# TRS-80.net
KiCad netlist of a schematic drawn in EAGLE
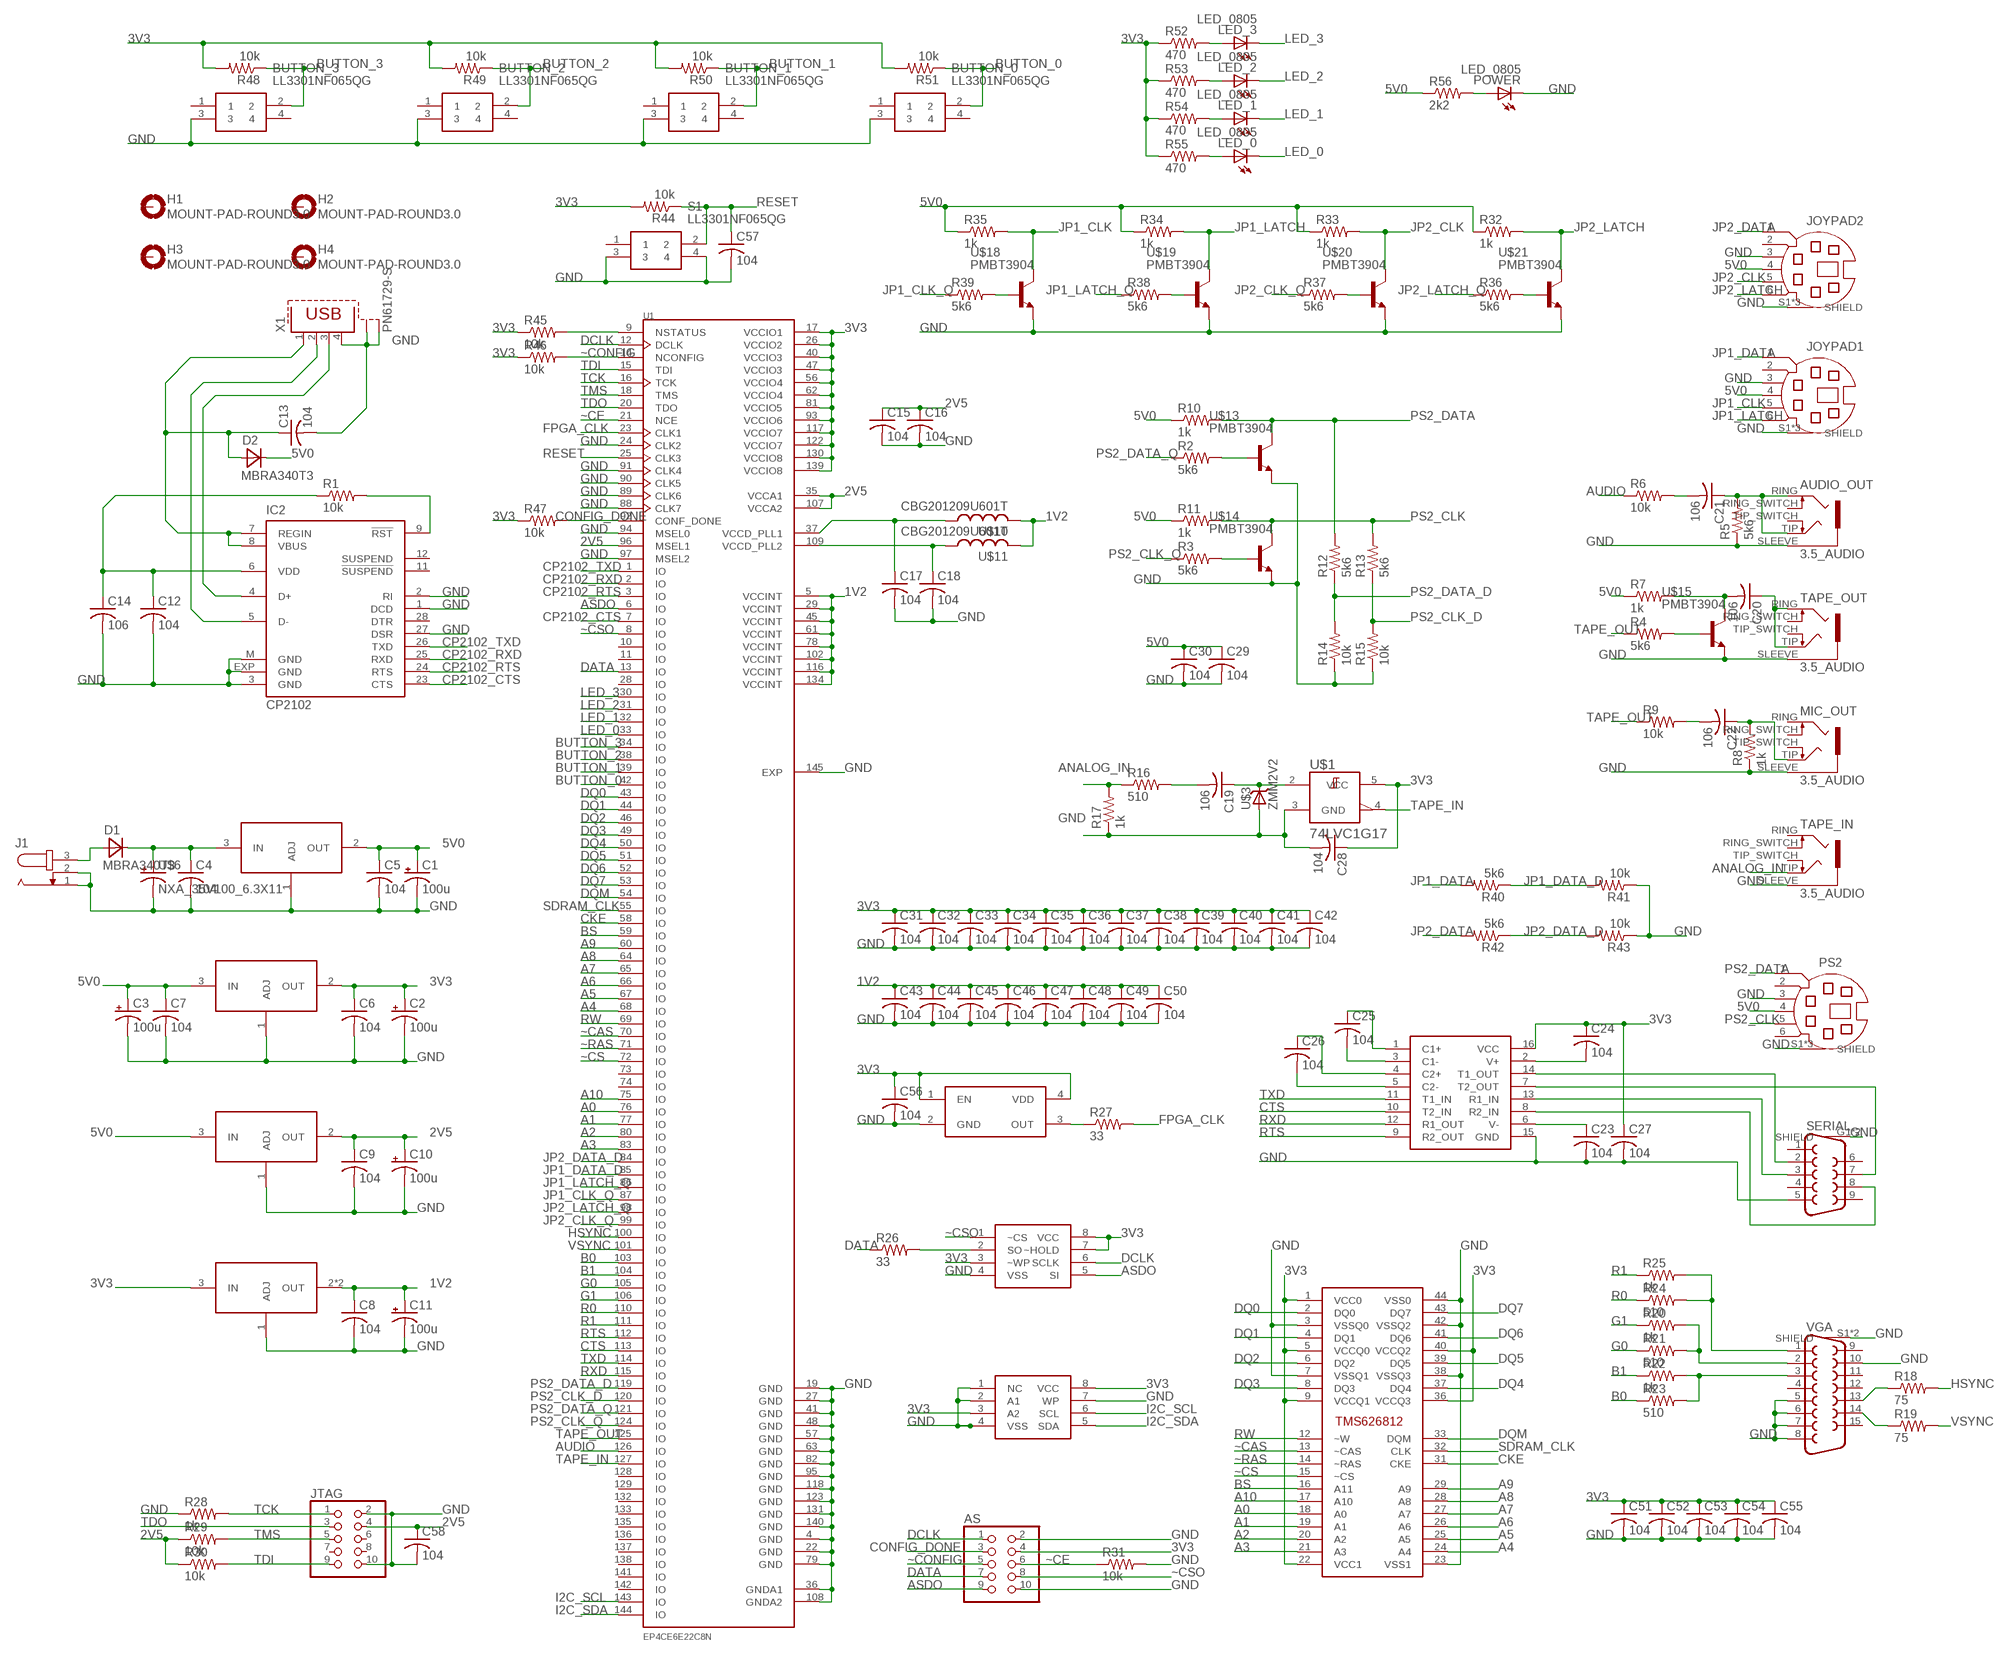
[diagram p0: schematic, sheet 1]

(export (version "E")
  (design (tool "Eeschema 10.0.6"))
  (components
    (comp (ref "AS")
      (value "PINHD-2X5")
      (footprint "eagle-import:2X05")
      (libsource (lib "eagle-import") (part "PINHD-2X5"))
    )
    (comp (ref "AUDIO_OUT")
      (value "3.5_AUDIO")
      (footprint "eagle-import:3.5_AUDIO")
      (libsource (lib "eagle-import") (part "3.5_AUDIO"))
    )
    (comp (ref "BUTTON_0")
      (value "LL3301NF065QG")
      (footprint "eagle-import:LL3301NF065QG")
      (fields (field (name "MOUSER_PART_NUMBER") "612-LL3301NF065QG"))
      (libsource (lib "eagle-import") (part "LL3301NF065QG"))
    )
    (comp (ref "BUTTON_1")
      (value "LL3301NF065QG")
      (footprint "eagle-import:LL3301NF065QG")
      (fields (field (name "MOUSER_PART_NUMBER") "612-LL3301NF065QG"))
      (libsource (lib "eagle-import") (part "LL3301NF065QG"))
    )
    (comp (ref "BUTTON_2")
      (value "LL3301NF065QG")
      (footprint "eagle-import:LL3301NF065QG")
      (fields (field (name "MOUSER_PART_NUMBER") "612-LL3301NF065QG"))
      (libsource (lib "eagle-import") (part "LL3301NF065QG"))
    )
    (comp (ref "BUTTON_3")
      (value "LL3301NF065QG")
      (footprint "eagle-import:LL3301NF065QG")
      (fields (field (name "MOUSER_PART_NUMBER") "612-LL3301NF065QG"))
      (libsource (lib "eagle-import") (part "LL3301NF065QG"))
    )
    (comp (ref "C1")
      (value "100u")
      (footprint "eagle-import:UD-6,3X5,8_NICHICON")
      (libsource (lib "eagle-import") (part "CPOL-USUD-6,3X5,8"))
    )
    (comp (ref "C2")
      (value "100u")
      (footprint "eagle-import:UD-6,3X5,8_NICHICON")
      (libsource (lib "eagle-import") (part "CPOL-USUD-6,3X5,8"))
    )
    (comp (ref "C3")
      (value "100u")
      (footprint "eagle-import:UD-6,3X5,8_NICHICON")
      (libsource (lib "eagle-import") (part "CPOL-USUD-6,3X5,8"))
    )
    (comp (ref "C4")
      (value "104")
      (footprint "eagle-import:C0805")
      (libsource (lib "eagle-import") (part "C-USC0805"))
    )
    (comp (ref "C5")
      (value "104")
      (footprint "eagle-import:C0805")
      (libsource (lib "eagle-import") (part "C-USC0805"))
    )
    (comp (ref "C6")
      (value "104")
      (footprint "eagle-import:C0805")
      (libsource (lib "eagle-import") (part "C-USC0805"))
    )
    (comp (ref "C7")
      (value "104")
      (footprint "eagle-import:C0805")
      (libsource (lib "eagle-import") (part "C-USC0805"))
    )
    (comp (ref "C8")
      (value "104")
      (footprint "eagle-import:C0805")
      (libsource (lib "eagle-import") (part "C-USC0805"))
    )
    (comp (ref "C9")
      (value "104")
      (footprint "eagle-import:C0805")
      (libsource (lib "eagle-import") (part "C-USC0805"))
    )
    (comp (ref "C10")
      (value "100u")
      (footprint "eagle-import:UD-6,3X5,8_NICHICON")
      (libsource (lib "eagle-import") (part "CPOL-USUD-6,3X5,8"))
    )
    (comp (ref "C11")
      (value "100u")
      (footprint "eagle-import:UD-6,3X5,8_NICHICON")
      (libsource (lib "eagle-import") (part "CPOL-USUD-6,3X5,8"))
    )
    (comp (ref "C12")
      (value "104")
      (footprint "eagle-import:C0805")
      (libsource (lib "eagle-import") (part "C-USC0805"))
    )
    (comp (ref "C13")
      (value "104")
      (footprint "eagle-import:C0805")
      (libsource (lib "eagle-import") (part "C-USC0805"))
    )
    (comp (ref "C14")
      (value "106")
      (footprint "eagle-import:C1206")
      (libsource (lib "eagle-import") (part "C-USC1206"))
    )
    (comp (ref "C15")
      (value "104")
      (footprint "eagle-import:C0805")
      (libsource (lib "eagle-import") (part "C-USC0805"))
    )
    (comp (ref "C16")
      (value "104")
      (footprint "eagle-import:C0805")
      (libsource (lib "eagle-import") (part "C-USC0805"))
    )
    (comp (ref "C17")
      (value "104")
      (footprint "eagle-import:C0805")
      (libsource (lib "eagle-import") (part "C-USC0805"))
    )
    (comp (ref "C18")
      (value "104")
      (footprint "eagle-import:C0805")
      (libsource (lib "eagle-import") (part "C-USC0805"))
    )
    (comp (ref "C19")
      (value "106")
      (footprint "eagle-import:C1206")
      (libsource (lib "eagle-import") (part "C-USC1206"))
    )
    (comp (ref "C20")
      (value "106")
      (footprint "eagle-import:C1206")
      (libsource (lib "eagle-import") (part "C-USC1206"))
    )
    (comp (ref "C21")
      (value "106")
      (footprint "eagle-import:C1206")
      (libsource (lib "eagle-import") (part "C-USC1206"))
    )
    (comp (ref "C22")
      (value "106")
      (footprint "eagle-import:C1206")
      (libsource (lib "eagle-import") (part "C-USC1206"))
    )
    (comp (ref "C23")
      (value "104")
      (footprint "eagle-import:C0805")
      (libsource (lib "eagle-import") (part "C-USC0805"))
    )
    (comp (ref "C24")
      (value "104")
      (footprint "eagle-import:C0805")
      (libsource (lib "eagle-import") (part "C-USC0805"))
    )
    (comp (ref "C25")
      (value "104")
      (footprint "eagle-import:C0805")
      (libsource (lib "eagle-import") (part "C-USC0805"))
    )
    (comp (ref "C26")
      (value "104")
      (footprint "eagle-import:C0805")
      (libsource (lib "eagle-import") (part "C-USC0805"))
    )
    (comp (ref "C27")
      (value "104")
      (footprint "eagle-import:C0805")
      (libsource (lib "eagle-import") (part "C-USC0805"))
    )
    (comp (ref "C28")
      (value "104")
      (footprint "eagle-import:C0805")
      (libsource (lib "eagle-import") (part "C-USC0805"))
    )
    (comp (ref "C29")
      (value "104")
      (footprint "eagle-import:C0805")
      (libsource (lib "eagle-import") (part "C-USC0805"))
    )
    (comp (ref "C30")
      (value "104")
      (footprint "eagle-import:C0805")
      (libsource (lib "eagle-import") (part "C-USC0805"))
    )
    (comp (ref "C31")
      (value "104")
      (footprint "eagle-import:C0805")
      (libsource (lib "eagle-import") (part "C-USC0805"))
    )
    (comp (ref "C32")
      (value "104")
      (footprint "eagle-import:C0805")
      (libsource (lib "eagle-import") (part "C-USC0805"))
    )
    (comp (ref "C33")
      (value "104")
      (footprint "eagle-import:C0805")
      (libsource (lib "eagle-import") (part "C-USC0805"))
    )
    (comp (ref "C34")
      (value "104")
      (footprint "eagle-import:C0805")
      (libsource (lib "eagle-import") (part "C-USC0805"))
    )
    (comp (ref "C35")
      (value "104")
      (footprint "eagle-import:C0805")
      (libsource (lib "eagle-import") (part "C-USC0805"))
    )
    (comp (ref "C36")
      (value "104")
      (footprint "eagle-import:C0805")
      (libsource (lib "eagle-import") (part "C-USC0805"))
    )
    (comp (ref "C37")
      (value "104")
      (footprint "eagle-import:C0805")
      (libsource (lib "eagle-import") (part "C-USC0805"))
    )
    (comp (ref "C38")
      (value "104")
      (footprint "eagle-import:C0805")
      (libsource (lib "eagle-import") (part "C-USC0805"))
    )
    (comp (ref "C39")
      (value "104")
      (footprint "eagle-import:C0805")
      (libsource (lib "eagle-import") (part "C-USC0805"))
    )
    (comp (ref "C40")
      (value "104")
      (footprint "eagle-import:C0805")
      (libsource (lib "eagle-import") (part "C-USC0805"))
    )
    (comp (ref "C41")
      (value "104")
      (footprint "eagle-import:C0805")
      (libsource (lib "eagle-import") (part "C-USC0805"))
    )
    (comp (ref "C42")
      (value "104")
      (footprint "eagle-import:C0805")
      (libsource (lib "eagle-import") (part "C-USC0805"))
    )
    (comp (ref "C43")
      (value "104")
      (footprint "eagle-import:C0805")
      (libsource (lib "eagle-import") (part "C-USC0805"))
    )
    (comp (ref "C44")
      (value "104")
      (footprint "eagle-import:C0805")
      (libsource (lib "eagle-import") (part "C-USC0805"))
    )
    (comp (ref "C45")
      (value "104")
      (footprint "eagle-import:C0805")
      (libsource (lib "eagle-import") (part "C-USC0805"))
    )
    (comp (ref "C46")
      (value "104")
      (footprint "eagle-import:C0805")
      (libsource (lib "eagle-import") (part "C-USC0805"))
    )
    (comp (ref "C47")
      (value "104")
      (footprint "eagle-import:C0805")
      (libsource (lib "eagle-import") (part "C-USC0805"))
    )
    (comp (ref "C48")
      (value "104")
      (footprint "eagle-import:C0805")
      (libsource (lib "eagle-import") (part "C-USC0805"))
    )
    (comp (ref "C49")
      (value "104")
      (footprint "eagle-import:C0805")
      (libsource (lib "eagle-import") (part "C-USC0805"))
    )
    (comp (ref "C50")
      (value "104")
      (footprint "eagle-import:C0805")
      (libsource (lib "eagle-import") (part "C-USC0805"))
    )
    (comp (ref "C51")
      (value "104")
      (footprint "eagle-import:C0805")
      (libsource (lib "eagle-import") (part "C-USC0805"))
    )
    (comp (ref "C52")
      (value "104")
      (footprint "eagle-import:C0805")
      (libsource (lib "eagle-import") (part "C-USC0805"))
    )
    (comp (ref "C53")
      (value "104")
      (footprint "eagle-import:C0805")
      (libsource (lib "eagle-import") (part "C-USC0805"))
    )
    (comp (ref "C54")
      (value "104")
      (footprint "eagle-import:C0805")
      (libsource (lib "eagle-import") (part "C-USC0805"))
    )
    (comp (ref "C55")
      (value "104")
      (footprint "eagle-import:C0805")
      (libsource (lib "eagle-import") (part "C-USC0805"))
    )
    (comp (ref "C56")
      (value "104")
      (footprint "eagle-import:C0805")
      (libsource (lib "eagle-import") (part "C-USC0805"))
    )
    (comp (ref "C57")
      (value "104")
      (footprint "eagle-import:C0805")
      (libsource (lib "eagle-import") (part "C-USC0805"))
    )
    (comp (ref "C58")
      (value "104")
      (footprint "eagle-import:C0805")
      (libsource (lib "eagle-import") (part "C-USC0805"))
    )
    (comp (ref "D1")
      (value "MBRA340T3")
      (footprint "eagle-import:SMA")
      (libsource (lib "eagle-import") (part "MBRA340T3"))
    )
    (comp (ref "D2")
      (value "MBRA340T3")
      (footprint "eagle-import:SMA")
      (libsource (lib "eagle-import") (part "MBRA340T3"))
    )
    (comp (ref "H1")
      (value "MOUNT-PAD-ROUND3.0")
      (footprint "eagle-import:3,0-PAD")
      (libsource (lib "eagle-import") (part "MOUNT-PAD-ROUND3.0"))
    )
    (comp (ref "H2")
      (value "MOUNT-PAD-ROUND3.0")
      (footprint "eagle-import:3,0-PAD")
      (libsource (lib "eagle-import") (part "MOUNT-PAD-ROUND3.0"))
    )
    (comp (ref "H3")
      (value "MOUNT-PAD-ROUND3.0")
      (footprint "eagle-import:3,0-PAD")
      (libsource (lib "eagle-import") (part "MOUNT-PAD-ROUND3.0"))
    )
    (comp (ref "H4")
      (value "MOUNT-PAD-ROUND3.0")
      (footprint "eagle-import:3,0-PAD")
      (libsource (lib "eagle-import") (part "MOUNT-PAD-ROUND3.0"))
    )
    (comp (ref "IC2")
      (value "CP2102")
      (footprint "eagle-import:MLP28")
      (fields (field (name "MF") "FARNELL") (field (name "MPN") "CP2102-GM"))
      (libsource (lib "eagle-import") (part "CP2102"))
    )
    (comp (ref "J1")
      (value "JACK-PLUG1")
      (footprint "eagle-import:SPC4078")
      (libsource (lib "eagle-import") (part "JACK-PLUG1"))
    )
    (comp (ref "JOYPAD1")
      (value "MD06SS")
      (footprint "eagle-import:MDIN06SS")
      (libsource (lib "eagle-import") (part "MD06SS"))
    )
    (comp (ref "JOYPAD2")
      (value "MD06SS")
      (footprint "eagle-import:MDIN06SS")
      (libsource (lib "eagle-import") (part "MD06SS"))
    )
    (comp (ref "JTAG")
      (value "PINHD-2X5")
      (footprint "eagle-import:2X05")
      (libsource (lib "eagle-import") (part "PINHD-2X5"))
    )
    (comp (ref "LED_0")
      (value "LED_0805")
      (footprint "eagle-import:CHIP-LED0805")
      (libsource (lib "eagle-import") (part "LED_0805"))
    )
    (comp (ref "LED_1")
      (value "LED_0805")
      (footprint "eagle-import:CHIP-LED0805")
      (libsource (lib "eagle-import") (part "LED_0805"))
    )
    (comp (ref "LED_2")
      (value "LED_0805")
      (footprint "eagle-import:CHIP-LED0805")
      (libsource (lib "eagle-import") (part "LED_0805"))
    )
    (comp (ref "LED_3")
      (value "LED_0805")
      (footprint "eagle-import:CHIP-LED0805")
      (libsource (lib "eagle-import") (part "LED_0805"))
    )
    (comp (ref "MIC_OUT")
      (value "3.5_AUDIO")
      (footprint "eagle-import:3.5_AUDIO")
      (libsource (lib "eagle-import") (part "3.5_AUDIO"))
    )
    (comp (ref "POWER")
      (value "LED_0805")
      (footprint "eagle-import:CHIP-LED0805")
      (libsource (lib "eagle-import") (part "LED_0805"))
    )
    (comp (ref "PS2")
      (value "MD06SS")
      (footprint "eagle-import:MDIN06SS")
      (libsource (lib "eagle-import") (part "MD06SS"))
    )
    (comp (ref "R1")
      (value "10k")
      (footprint "eagle-import:R0805")
      (libsource (lib "eagle-import") (part "R-US_R0805"))
    )
    (comp (ref "R2")
      (value "5k6")
      (footprint "eagle-import:R0805")
      (libsource (lib "eagle-import") (part "R-US_R0805"))
    )
    (comp (ref "R3")
      (value "5k6")
      (footprint "eagle-import:R0805")
      (libsource (lib "eagle-import") (part "R-US_R0805"))
    )
    (comp (ref "R4")
      (value "5k6")
      (footprint "eagle-import:R0805")
      (libsource (lib "eagle-import") (part "R-US_R0805"))
    )
    (comp (ref "R5")
      (value "5k6")
      (footprint "eagle-import:R0805")
      (libsource (lib "eagle-import") (part "R-US_R0805"))
    )
    (comp (ref "R6")
      (value "10k")
      (footprint "eagle-import:R0805")
      (libsource (lib "eagle-import") (part "R-US_R0805"))
    )
    (comp (ref "R7")
      (value "1k")
      (footprint "eagle-import:R0805")
      (libsource (lib "eagle-import") (part "R-US_R0805"))
    )
    (comp (ref "R8")
      (value "1k")
      (footprint "eagle-import:R0805")
      (libsource (lib "eagle-import") (part "R-US_R0805"))
    )
    (comp (ref "R9")
      (value "10k")
      (footprint "eagle-import:R0805")
      (libsource (lib "eagle-import") (part "R-US_R0805"))
    )
    (comp (ref "R10")
      (value "1k")
      (footprint "eagle-import:R0805")
      (libsource (lib "eagle-import") (part "R-US_R0805"))
    )
    (comp (ref "R11")
      (value "1k")
      (footprint "eagle-import:R0805")
      (libsource (lib "eagle-import") (part "R-US_R0805"))
    )
    (comp (ref "R12")
      (value "5k6")
      (footprint "eagle-import:R0805")
      (libsource (lib "eagle-import") (part "R-US_R0805"))
    )
    (comp (ref "R13")
      (value "5k6")
      (footprint "eagle-import:R0805")
      (libsource (lib "eagle-import") (part "R-US_R0805"))
    )
    (comp (ref "R14")
      (value "10k")
      (footprint "eagle-import:R0805")
      (libsource (lib "eagle-import") (part "R-US_R0805"))
    )
    (comp (ref "R15")
      (value "10k")
      (footprint "eagle-import:R0805")
      (libsource (lib "eagle-import") (part "R-US_R0805"))
    )
    (comp (ref "R16")
      (value "510")
      (footprint "eagle-import:R0805")
      (libsource (lib "eagle-import") (part "R-US_R0805"))
    )
    (comp (ref "R17")
      (value "1k")
      (footprint "eagle-import:R0805")
      (libsource (lib "eagle-import") (part "R-US_R0805"))
    )
    (comp (ref "R18")
      (value "75")
      (footprint "eagle-import:R0805")
      (libsource (lib "eagle-import") (part "R-US_R0805"))
    )
    (comp (ref "R19")
      (value "75")
      (footprint "eagle-import:R0805")
      (libsource (lib "eagle-import") (part "R-US_R0805"))
    )
    (comp (ref "R20")
      (value "1k")
      (footprint "eagle-import:R0805")
      (libsource (lib "eagle-import") (part "R-US_R0805"))
    )
    (comp (ref "R21")
      (value "510")
      (footprint "eagle-import:R0805")
      (libsource (lib "eagle-import") (part "R-US_R0805"))
    )
    (comp (ref "R22")
      (value "1k")
      (footprint "eagle-import:R0805")
      (libsource (lib "eagle-import") (part "R-US_R0805"))
    )
    (comp (ref "R23")
      (value "510")
      (footprint "eagle-import:R0805")
      (libsource (lib "eagle-import") (part "R-US_R0805"))
    )
    (comp (ref "R24")
      (value "510")
      (footprint "eagle-import:R0805")
      (libsource (lib "eagle-import") (part "R-US_R0805"))
    )
    (comp (ref "R25")
      (value "1k")
      (footprint "eagle-import:R0805")
      (libsource (lib "eagle-import") (part "R-US_R0805"))
    )
    (comp (ref "R26")
      (value "33")
      (footprint "eagle-import:R0805")
      (libsource (lib "eagle-import") (part "R-US_R0805"))
    )
    (comp (ref "R27")
      (value "33")
      (footprint "eagle-import:R0805")
      (libsource (lib "eagle-import") (part "R-US_R0805"))
    )
    (comp (ref "R28")
      (value "1k")
      (footprint "eagle-import:R0805")
      (libsource (lib "eagle-import") (part "R-US_R0805"))
    )
    (comp (ref "R29")
      (value "10k")
      (footprint "eagle-import:R0805")
      (libsource (lib "eagle-import") (part "R-US_R0805"))
    )
    (comp (ref "R30")
      (value "10k")
      (footprint "eagle-import:R0805")
      (libsource (lib "eagle-import") (part "R-US_R0805"))
    )
    (comp (ref "R31")
      (value "10k")
      (footprint "eagle-import:R0805")
      (libsource (lib "eagle-import") (part "R-US_R0805"))
    )
    (comp (ref "R32")
      (value "1k")
      (footprint "eagle-import:R0805")
      (libsource (lib "eagle-import") (part "R-US_R0805"))
    )
    (comp (ref "R33")
      (value "1k")
      (footprint "eagle-import:R0805")
      (libsource (lib "eagle-import") (part "R-US_R0805"))
    )
    (comp (ref "R34")
      (value "1k")
      (footprint "eagle-import:R0805")
      (libsource (lib "eagle-import") (part "R-US_R0805"))
    )
    (comp (ref "R35")
      (value "1k")
      (footprint "eagle-import:R0805")
      (libsource (lib "eagle-import") (part "R-US_R0805"))
    )
    (comp (ref "R36")
      (value "5k6")
      (footprint "eagle-import:R0805")
      (libsource (lib "eagle-import") (part "R-US_R0805"))
    )
    (comp (ref "R37")
      (value "5k6")
      (footprint "eagle-import:R0805")
      (libsource (lib "eagle-import") (part "R-US_R0805"))
    )
    (comp (ref "R38")
      (value "5k6")
      (footprint "eagle-import:R0805")
      (libsource (lib "eagle-import") (part "R-US_R0805"))
    )
    (comp (ref "R39")
      (value "5k6")
      (footprint "eagle-import:R0805")
      (libsource (lib "eagle-import") (part "R-US_R0805"))
    )
    (comp (ref "R40")
      (value "5k6")
      (footprint "eagle-import:R0805")
      (libsource (lib "eagle-import") (part "R-US_R0805"))
    )
    (comp (ref "R41")
      (value "10k")
      (footprint "eagle-import:R0805")
      (libsource (lib "eagle-import") (part "R-US_R0805"))
    )
    (comp (ref "R42")
      (value "5k6")
      (footprint "eagle-import:R0805")
      (libsource (lib "eagle-import") (part "R-US_R0805"))
    )
    (comp (ref "R43")
      (value "10k")
      (footprint "eagle-import:R0805")
      (libsource (lib "eagle-import") (part "R-US_R0805"))
    )
    (comp (ref "R44")
      (value "10k")
      (footprint "eagle-import:R0805")
      (libsource (lib "eagle-import") (part "R-US_R0805"))
    )
    (comp (ref "R45")
      (value "10k")
      (footprint "eagle-import:R0805")
      (libsource (lib "eagle-import") (part "R-US_R0805"))
    )
    (comp (ref "R46")
      (value "10k")
      (footprint "eagle-import:R0805")
      (libsource (lib "eagle-import") (part "R-US_R0805"))
    )
    (comp (ref "R47")
      (value "10k")
      (footprint "eagle-import:R0805")
      (libsource (lib "eagle-import") (part "R-US_R0805"))
    )
    (comp (ref "R48")
      (value "10k")
      (footprint "eagle-import:R0805")
      (libsource (lib "eagle-import") (part "R-US_R0805"))
    )
    (comp (ref "R49")
      (value "10k")
      (footprint "eagle-import:R0805")
      (libsource (lib "eagle-import") (part "R-US_R0805"))
    )
    (comp (ref "R50")
      (value "10k")
      (footprint "eagle-import:R0805")
      (libsource (lib "eagle-import") (part "R-US_R0805"))
    )
    (comp (ref "R51")
      (value "10k")
      (footprint "eagle-import:R0805")
      (libsource (lib "eagle-import") (part "R-US_R0805"))
    )
    (comp (ref "R52")
      (value "470")
      (footprint "eagle-import:R0805")
      (libsource (lib "eagle-import") (part "R-US_R0805"))
    )
    (comp (ref "R53")
      (value "470")
      (footprint "eagle-import:R0805")
      (libsource (lib "eagle-import") (part "R-US_R0805"))
    )
    (comp (ref "R54")
      (value "470")
      (footprint "eagle-import:R0805")
      (libsource (lib "eagle-import") (part "R-US_R0805"))
    )
    (comp (ref "R55")
      (value "470")
      (footprint "eagle-import:R0805")
      (libsource (lib "eagle-import") (part "R-US_R0805"))
    )
    (comp (ref "R56")
      (value "2k2")
      (footprint "eagle-import:R0805")
      (libsource (lib "eagle-import") (part "R-US_R0805"))
    )
    (comp (ref "S1")
      (value "LL3301NF065QG")
      (footprint "eagle-import:LL3301NF065QG")
      (fields (field (name "MOUSER_PART_NUMBER") "612-LL3301NF065QG"))
      (libsource (lib "eagle-import") (part "LL3301NF065QG"))
    )
    (comp (ref "SERIAL")
      (value "F09HP")
      (footprint "eagle-import:F09HP")
      (libsource (lib "eagle-import") (part "F09HP"))
    )
    (comp (ref "TAPE_IN")
      (value "3.5_AUDIO")
      (footprint "eagle-import:3.5_AUDIO")
      (libsource (lib "eagle-import") (part "3.5_AUDIO"))
    )
    (comp (ref "TAPE_OUT")
      (value "3.5_AUDIO")
      (footprint "eagle-import:3.5_AUDIO")
      (libsource (lib "eagle-import") (part "3.5_AUDIO"))
    )
    (comp (ref "U$1")
      (value "74LVC1G17")
      (footprint "eagle-import:SOT353")
      (libsource (lib "eagle-import") (part "74LVC1G17"))
    )
    (comp (ref "U$2")
      (value "TMS626812")
      (footprint "eagle-import:TSOP44-II")
      (libsource (lib "eagle-import") (part "TMS626812"))
    )
    (comp (ref "U$3")
      (value "ZMM2V2")
      (footprint "eagle-import:SOD80C")
      (libsource (lib "eagle-import") (part "ZMM2V2"))
    )
    (comp (ref "U$4")
      (value "SP232")
      (footprint "eagle-import:SOP16")
      (libsource (lib "eagle-import") (part "SP232"))
    )
    (comp (ref "U$5")
      (value "LM1086")
      (footprint "eagle-import:D2PACK")
      (libsource (lib "eagle-import") (part "LM1086"))
    )
    (comp (ref "U$6")
      (value "NXA_35V100_6.3X11")
      (footprint "eagle-import:NXA_35V100_6.3X11")
      (libsource (lib "eagle-import") (part "NXA_35V100_6.3X11"))
    )
    (comp (ref "U$7")
      (value "LD1117D-3.3")
      (footprint "eagle-import:TO252")
      (libsource (lib "eagle-import") (part "LD1117D-3.3"))
    )
    (comp (ref "U$8")
      (value "KIA1117-2.5")
      (footprint "eagle-import:SOT223")
      (libsource (lib "eagle-import") (part "KIA1117-2.5"))
    )
    (comp (ref "U$9")
      (value "AZ1117H-1.2TRG1")
      (footprint "eagle-import:SOT223")
      (libsource (lib "eagle-import") (part "AZ1117H-1.2TRG1"))
    )
    (comp (ref "U$10")
      (value "CBG201209U601T")
      (footprint "eagle-import:C0805")
      (libsource (lib "eagle-import") (part "CBG201209U601T"))
    )
    (comp (ref "U$11")
      (value "CBG201209U601T")
      (footprint "eagle-import:C0805")
      (libsource (lib "eagle-import") (part "CBG201209U601T"))
    )
    (comp (ref "U$12")
      (value "OT705050MJBA4SL")
      (footprint "eagle-import:ASV32000MHZET")
      (libsource (lib "eagle-import") (part "OT705050MJBA4SL"))
    )
    (comp (ref "U$13")
      (value "PMBT3904")
      (footprint "eagle-import:SOT23")
      (libsource (lib "eagle-import") (part "PMBT3904"))
    )
    (comp (ref "U$14")
      (value "PMBT3904")
      (footprint "eagle-import:SOT23")
      (libsource (lib "eagle-import") (part "PMBT3904"))
    )
    (comp (ref "U$15")
      (value "PMBT3904")
      (footprint "eagle-import:SOT23")
      (libsource (lib "eagle-import") (part "PMBT3904"))
    )
    (comp (ref "U$16")
      (value "BY25Q16BS")
      (footprint "eagle-import:SO08")
      (libsource (lib "eagle-import") (part "BY25Q16BS"))
    )
    (comp (ref "U$17")
      (value "CAT24M01WI-GT3")
      (footprint "eagle-import:SO08")
      (libsource (lib "eagle-import") (part "CAT24M01WI-GT3"))
    )
    (comp (ref "U$18")
      (value "PMBT3904")
      (footprint "eagle-import:SOT23")
      (libsource (lib "eagle-import") (part "PMBT3904"))
    )
    (comp (ref "U$19")
      (value "PMBT3904")
      (footprint "eagle-import:SOT23")
      (libsource (lib "eagle-import") (part "PMBT3904"))
    )
    (comp (ref "U$20")
      (value "PMBT3904")
      (footprint "eagle-import:SOT23")
      (libsource (lib "eagle-import") (part "PMBT3904"))
    )
    (comp (ref "U$21")
      (value "PMBT3904")
      (footprint "eagle-import:SOT23")
      (libsource (lib "eagle-import") (part "PMBT3904"))
    )
    (comp (ref "U1")
      (value "EP4CE6E22C8N")
      (footprint "eagle-import:QFP50P2200X2200X165-145N")
      (fields (field (name "MF") "Intel"))
      (libsource (lib "eagle-import") (part "EP4CE6E22C8N"))
    )
    (comp (ref "VGA")
      (value "F15HDH")
      (footprint "eagle-import:HDF15H")
      (libsource (lib "eagle-import") (part "F15HDH"))
    )
    (comp (ref "X1")
      (value "PN61729-S")
      (footprint "eagle-import:PN61729-S")
      (libsource (lib "eagle-import") (part "PN61729-S"))
    )
  )
  (nets
    (net (code "1") (name "/1V2") (class "Default")
      (node (ref "C11") (pin "+") (pinfunction "+_+") (pintype "passive"))
      (node (ref "C43") (pin "1") (pinfunction "1_1") (pintype "passive"))
      (node (ref "C44") (pin "1") (pinfunction "1_1") (pintype "passive"))
      (node (ref "C45") (pin "1") (pinfunction "1_1") (pintype "passive"))
      (node (ref "C46") (pin "1") (pinfunction "1_1") (pintype "passive"))
      (node (ref "C47") (pin "1") (pinfunction "1_1") (pintype "passive"))
      (node (ref "C48") (pin "1") (pinfunction "1_1") (pintype "passive"))
      (node (ref "C49") (pin "1") (pinfunction "1_1") (pintype "passive"))
      (node (ref "C50") (pin "1") (pinfunction "1_1") (pintype "passive"))
      (node (ref "C8") (pin "1") (pinfunction "1_1") (pintype "passive"))
      (node (ref "U$10") (pin "2") (pinfunction "2_2") (pintype "passive"))
      (node (ref "U$11") (pin "2") (pinfunction "2_2") (pintype "passive"))
      (node (ref "U$9") (pin "2") (pinfunction "OUT_2") (pintype "bidirectional"))
      (node (ref "U$9") (pin "4") (pinfunction "OUT_4") (pintype "bidirectional"))
      (node (ref "U1") (pin "102") (pinfunction "VCCINT_102") (pintype "power_in"))
      (node (ref "U1") (pin "116") (pinfunction "VCCINT_116") (pintype "power_in"))
      (node (ref "U1") (pin "134") (pinfunction "VCCINT_134") (pintype "power_in"))
      (node (ref "U1") (pin "29") (pinfunction "VCCINT_29") (pintype "power_in"))
      (node (ref "U1") (pin "45") (pinfunction "VCCINT_45") (pintype "power_in"))
      (node (ref "U1") (pin "5") (pinfunction "VCCINT_5") (pintype "power_in"))
      (node (ref "U1") (pin "61") (pinfunction "VCCINT_61") (pintype "power_in"))
      (node (ref "U1") (pin "78") (pinfunction "VCCINT_78") (pintype "power_in"))
    )
    (net (code "2") (name "/2V5") (class "Default")
      (node (ref "C10") (pin "+") (pinfunction "+_+") (pintype "passive"))
      (node (ref "C15") (pin "1") (pinfunction "1_1") (pintype "passive"))
      (node (ref "C16") (pin "1") (pinfunction "1_1") (pintype "passive"))
      (node (ref "C58") (pin "1") (pinfunction "1_1") (pintype "passive"))
      (node (ref "C9") (pin "1") (pinfunction "1_1") (pintype "passive"))
      (node (ref "JTAG") (pin "4") (pinfunction "4_4") (pintype "passive"))
      (node (ref "R29") (pin "1") (pinfunction "1_1") (pintype "passive"))
      (node (ref "R30") (pin "1") (pinfunction "1_1") (pintype "passive"))
      (node (ref "U$8") (pin "2") (pinfunction "OUT_2") (pintype "bidirectional"))
      (node (ref "U1") (pin "107") (pinfunction "VCCA2_107") (pintype "power_in"))
      (node (ref "U1") (pin "35") (pinfunction "VCCA1_35") (pintype "power_in"))
      (node (ref "U1") (pin "96") (pinfunction "MSEL1_96") (pintype "bidirectional"))
    )
    (net (code "3") (name "/3V3") (class "Default")
      (node (ref "AS") (pin "4") (pinfunction "4_4") (pintype "passive"))
      (node (ref "C2") (pin "+") (pinfunction "+_+") (pintype "passive"))
      (node (ref "C24") (pin "1") (pinfunction "1_1") (pintype "passive"))
      (node (ref "C27") (pin "1") (pinfunction "1_1") (pintype "passive"))
      (node (ref "C28") (pin "1") (pinfunction "1_1") (pintype "passive"))
      (node (ref "C31") (pin "1") (pinfunction "1_1") (pintype "passive"))
      (node (ref "C32") (pin "1") (pinfunction "1_1") (pintype "passive"))
      (node (ref "C33") (pin "1") (pinfunction "1_1") (pintype "passive"))
      (node (ref "C34") (pin "1") (pinfunction "1_1") (pintype "passive"))
      (node (ref "C35") (pin "1") (pinfunction "1_1") (pintype "passive"))
      (node (ref "C36") (pin "1") (pinfunction "1_1") (pintype "passive"))
      (node (ref "C37") (pin "1") (pinfunction "1_1") (pintype "passive"))
      (node (ref "C38") (pin "1") (pinfunction "1_1") (pintype "passive"))
      (node (ref "C39") (pin "1") (pinfunction "1_1") (pintype "passive"))
      (node (ref "C40") (pin "1") (pinfunction "1_1") (pintype "passive"))
      (node (ref "C41") (pin "1") (pinfunction "1_1") (pintype "passive"))
      (node (ref "C42") (pin "1") (pinfunction "1_1") (pintype "passive"))
      (node (ref "C51") (pin "1") (pinfunction "1_1") (pintype "passive"))
      (node (ref "C52") (pin "1") (pinfunction "1_1") (pintype "passive"))
      (node (ref "C53") (pin "1") (pinfunction "1_1") (pintype "passive"))
      (node (ref "C54") (pin "1") (pinfunction "1_1") (pintype "passive"))
      (node (ref "C55") (pin "1") (pinfunction "1_1") (pintype "passive"))
      (node (ref "C56") (pin "1") (pinfunction "1_1") (pintype "passive"))
      (node (ref "C6") (pin "1") (pinfunction "1_1") (pintype "passive"))
      (node (ref "R44") (pin "2") (pinfunction "2_2") (pintype "passive"))
      (node (ref "R45") (pin "1") (pinfunction "1_1") (pintype "passive"))
      (node (ref "R46") (pin "1") (pinfunction "1_1") (pintype "passive"))
      (node (ref "R47") (pin "1") (pinfunction "1_1") (pintype "passive"))
      (node (ref "R48") (pin "2") (pinfunction "2_2") (pintype "passive"))
      (node (ref "R49") (pin "2") (pinfunction "2_2") (pintype "passive"))
      (node (ref "R50") (pin "2") (pinfunction "2_2") (pintype "passive"))
      (node (ref "R51") (pin "2") (pinfunction "2_2") (pintype "passive"))
      (node (ref "R52") (pin "1") (pinfunction "1_1") (pintype "passive"))
      (node (ref "R53") (pin "1") (pinfunction "1_1") (pintype "passive"))
      (node (ref "R54") (pin "1") (pinfunction "1_1") (pintype "passive"))
      (node (ref "R55") (pin "1") (pinfunction "1_1") (pintype "passive"))
      (node (ref "U$1") (pin "5") (pinfunction "VCC_5") (pintype "power_in"))
      (node (ref "U$12") (pin "1") (pinfunction "EN_1") (pintype "bidirectional"))
      (node (ref "U$12") (pin "4") (pinfunction "VDD_4") (pintype "bidirectional"))
      (node (ref "U$16") (pin "3") (pinfunction "~{WP}_3") (pintype "bidirectional"))
      (node (ref "U$16") (pin "7") (pinfunction "~{HOLD}_7") (pintype "bidirectional"))
      (node (ref "U$16") (pin "8") (pinfunction "VCC_8") (pintype "bidirectional"))
      (node (ref "U$17") (pin "3") (pinfunction "A2_3") (pintype "bidirectional"))
      (node (ref "U$17") (pin "8") (pinfunction "VCC_8") (pintype "bidirectional"))
      (node (ref "U$2") (pin "1") (pinfunction "VCC0_1") (pintype "bidirectional"))
      (node (ref "U$2") (pin "22") (pinfunction "VCC1_22") (pintype "bidirectional"))
      (node (ref "U$2") (pin "36") (pinfunction "VCCQ3_36") (pintype "bidirectional"))
      (node (ref "U$2") (pin "40") (pinfunction "VCCQ2_40") (pintype "bidirectional"))
      (node (ref "U$2") (pin "5") (pinfunction "VCCQ0_5") (pintype "bidirectional"))
      (node (ref "U$2") (pin "9") (pinfunction "VCCQ1_9") (pintype "bidirectional"))
      (node (ref "U$4") (pin "16") (pinfunction "VCC_16") (pintype "bidirectional"))
      (node (ref "U$7") (pin "2") (pinfunction "OUT_2") (pintype "bidirectional"))
      (node (ref "U$9") (pin "3") (pinfunction "IN_3") (pintype "bidirectional"))
      (node (ref "U1") (pin "117") (pinfunction "VCCIO7_117") (pintype "power_in"))
      (node (ref "U1") (pin "122") (pinfunction "VCCIO7_122") (pintype "power_in"))
      (node (ref "U1") (pin "130") (pinfunction "VCCIO8_130") (pintype "power_in"))
      (node (ref "U1") (pin "139") (pinfunction "VCCIO8_139") (pintype "power_in"))
      (node (ref "U1") (pin "17") (pinfunction "VCCIO1_17") (pintype "power_in"))
      (node (ref "U1") (pin "26") (pinfunction "VCCIO2_26") (pintype "power_in"))
      (node (ref "U1") (pin "40") (pinfunction "VCCIO3_40") (pintype "power_in"))
      (node (ref "U1") (pin "47") (pinfunction "VCCIO3_47") (pintype "power_in"))
      (node (ref "U1") (pin "56") (pinfunction "VCCIO4_56") (pintype "power_in"))
      (node (ref "U1") (pin "62") (pinfunction "VCCIO4_62") (pintype "power_in"))
      (node (ref "U1") (pin "81") (pinfunction "VCCIO5_81") (pintype "power_in"))
      (node (ref "U1") (pin "93") (pinfunction "VCCIO6_93") (pintype "power_in"))
    )
    (net (code "4") (name "/5V0") (class "Default")
      (node (ref "C1") (pin "+") (pinfunction "+_+") (pintype "passive"))
      (node (ref "C29") (pin "1") (pinfunction "1_1") (pintype "passive"))
      (node (ref "C3") (pin "+") (pinfunction "+_+") (pintype "passive"))
      (node (ref "C30") (pin "1") (pinfunction "1_1") (pintype "passive"))
      (node (ref "C5") (pin "1") (pinfunction "1_1") (pintype "passive"))
      (node (ref "C7") (pin "1") (pinfunction "1_1") (pintype "passive"))
      (node (ref "D2") (pin "C") (pinfunction "C_C") (pintype "passive"))
      (node (ref "JOYPAD1") (pin "4") (pinfunction "4_4") (pintype "passive"))
      (node (ref "JOYPAD2") (pin "4") (pinfunction "4_4") (pintype "passive"))
      (node (ref "PS2") (pin "4") (pinfunction "4_4") (pintype "passive"))
      (node (ref "R10") (pin "1") (pinfunction "1_1") (pintype "passive"))
      (node (ref "R11") (pin "1") (pinfunction "1_1") (pintype "passive"))
      (node (ref "R32") (pin "1") (pinfunction "1_1") (pintype "passive"))
      (node (ref "R33") (pin "1") (pinfunction "1_1") (pintype "passive"))
      (node (ref "R34") (pin "1") (pinfunction "1_1") (pintype "passive"))
      (node (ref "R35") (pin "1") (pinfunction "1_1") (pintype "passive"))
      (node (ref "R56") (pin "1") (pinfunction "1_1") (pintype "passive"))
      (node (ref "R7") (pin "1") (pinfunction "1_1") (pintype "passive"))
      (node (ref "U$5") (pin "2") (pinfunction "OUT_2") (pintype "bidirectional"))
      (node (ref "U$7") (pin "3") (pinfunction "IN_3") (pintype "bidirectional"))
      (node (ref "U$8") (pin "3") (pinfunction "IN_3") (pintype "bidirectional"))
    )
    (net (code "5") (name "/A0") (class "Default")
      (node (ref "U$2") (pin "18") (pinfunction "A0_18") (pintype "bidirectional"))
      (node (ref "U1") (pin "76") (pinfunction "IO_76") (pintype "bidirectional"))
    )
    (net (code "6") (name "/A1") (class "Default")
      (node (ref "U$2") (pin "19") (pinfunction "A1_19") (pintype "bidirectional"))
      (node (ref "U1") (pin "77") (pinfunction "IO_77") (pintype "bidirectional"))
    )
    (net (code "7") (name "/A2") (class "Default")
      (node (ref "U$2") (pin "20") (pinfunction "A2_20") (pintype "bidirectional"))
      (node (ref "U1") (pin "80") (pinfunction "IO_80") (pintype "bidirectional"))
    )
    (net (code "8") (name "/A3") (class "Default")
      (node (ref "U$2") (pin "21") (pinfunction "A3_21") (pintype "bidirectional"))
      (node (ref "U1") (pin "83") (pinfunction "IO_83") (pintype "bidirectional"))
    )
    (net (code "9") (name "/A4") (class "Default")
      (node (ref "U$2") (pin "24") (pinfunction "A4_24") (pintype "bidirectional"))
      (node (ref "U1") (pin "68") (pinfunction "IO_68") (pintype "bidirectional"))
    )
    (net (code "10") (name "/A5") (class "Default")
      (node (ref "U$2") (pin "25") (pinfunction "A5_25") (pintype "bidirectional"))
      (node (ref "U1") (pin "67") (pinfunction "IO_67") (pintype "bidirectional"))
    )
    (net (code "11") (name "/A6") (class "Default")
      (node (ref "U$2") (pin "26") (pinfunction "A6_26") (pintype "bidirectional"))
      (node (ref "U1") (pin "66") (pinfunction "IO_66") (pintype "bidirectional"))
    )
    (net (code "12") (name "/A7") (class "Default")
      (node (ref "U$2") (pin "27") (pinfunction "A7_27") (pintype "bidirectional"))
      (node (ref "U1") (pin "65") (pinfunction "IO_65") (pintype "bidirectional"))
    )
    (net (code "13") (name "/A8") (class "Default")
      (node (ref "U$2") (pin "28") (pinfunction "A8_28") (pintype "bidirectional"))
      (node (ref "U1") (pin "64") (pinfunction "IO_64") (pintype "bidirectional"))
    )
    (net (code "14") (name "/A9") (class "Default")
      (node (ref "U$2") (pin "29") (pinfunction "A9_29") (pintype "bidirectional"))
      (node (ref "U1") (pin "60") (pinfunction "IO_60") (pintype "bidirectional"))
    )
    (net (code "15") (name "/A10") (class "Default")
      (node (ref "U$2") (pin "17") (pinfunction "A10_17") (pintype "bidirectional"))
      (node (ref "U1") (pin "75") (pinfunction "IO_75") (pintype "bidirectional"))
    )
    (net (code "16") (name "/ANALOG_IN") (class "Default")
      (node (ref "R16") (pin "1") (pinfunction "1_1") (pintype "passive"))
      (node (ref "R17") (pin "2") (pinfunction "2_2") (pintype "passive"))
      (node (ref "TAPE_IN") (pin "TIP") (pinfunction "TIP_TIP") (pintype "passive"))
    )
    (net (code "17") (name "/ASDO") (class "Default")
      (node (ref "AS") (pin "9") (pinfunction "9_9") (pintype "passive"))
      (node (ref "U$16") (pin "5") (pinfunction "SI_5") (pintype "bidirectional"))
      (node (ref "U1") (pin "6") (pinfunction "IO_6") (pintype "bidirectional"))
    )
    (net (code "18") (name "/AUDIO") (class "Default")
      (node (ref "R6") (pin "1") (pinfunction "1_1") (pintype "passive"))
      (node (ref "U1") (pin "126") (pinfunction "IO_126") (pintype "bidirectional"))
    )
    (net (code "19") (name "/B0") (class "Default")
      (node (ref "R23") (pin "1") (pinfunction "1_1") (pintype "passive"))
      (node (ref "U1") (pin "103") (pinfunction "IO_103") (pintype "bidirectional"))
    )
    (net (code "20") (name "/B1") (class "Default")
      (node (ref "R22") (pin "1") (pinfunction "1_1") (pintype "passive"))
      (node (ref "U1") (pin "104") (pinfunction "IO_104") (pintype "bidirectional"))
    )
    (net (code "21") (name "/BS") (class "Default")
      (node (ref "U$2") (pin "16") (pinfunction "A11_16") (pintype "bidirectional"))
      (node (ref "U1") (pin "59") (pinfunction "IO_59") (pintype "bidirectional"))
    )
    (net (code "22") (name "/BUTTON_0") (class "Default")
      (node (ref "BUTTON_0") (pin "2") (pinfunction "2_2") (pintype "bidirectional"))
      (node (ref "R51") (pin "1") (pinfunction "1_1") (pintype "passive"))
      (node (ref "U1") (pin "42") (pinfunction "IO_42") (pintype "bidirectional"))
    )
    (net (code "23") (name "/BUTTON_1") (class "Default")
      (node (ref "BUTTON_1") (pin "2") (pinfunction "2_2") (pintype "bidirectional"))
      (node (ref "R50") (pin "1") (pinfunction "1_1") (pintype "passive"))
      (node (ref "U1") (pin "39") (pinfunction "IO_39") (pintype "bidirectional"))
    )
    (net (code "24") (name "/BUTTON_2") (class "Default")
      (node (ref "BUTTON_2") (pin "2") (pinfunction "2_2") (pintype "bidirectional"))
      (node (ref "R49") (pin "1") (pinfunction "1_1") (pintype "passive"))
      (node (ref "U1") (pin "38") (pinfunction "IO_38") (pintype "bidirectional"))
    )
    (net (code "25") (name "/BUTTON_3") (class "Default")
      (node (ref "BUTTON_3") (pin "2") (pinfunction "2_2") (pintype "bidirectional"))
      (node (ref "R48") (pin "1") (pinfunction "1_1") (pintype "passive"))
      (node (ref "U1") (pin "34") (pinfunction "IO_34") (pintype "bidirectional"))
    )
    (net (code "26") (name "/CKE") (class "Default")
      (node (ref "U$2") (pin "31") (pinfunction "CKE_31") (pintype "bidirectional"))
      (node (ref "U1") (pin "58") (pinfunction "IO_58") (pintype "bidirectional"))
    )
    (net (code "27") (name "/CONFIG_DONE") (class "Default")
      (node (ref "AS") (pin "3") (pinfunction "3_3") (pintype "passive"))
      (node (ref "R47") (pin "2") (pinfunction "2_2") (pintype "passive"))
      (node (ref "U1") (pin "92") (pinfunction "CONF_DONE_92") (pintype "bidirectional"))
    )
    (net (code "28") (name "/CP2102_CTS") (class "Default")
      (node (ref "IC2") (pin "23") (pinfunction "CTS_23") (pintype "input"))
      (node (ref "U1") (pin "7") (pinfunction "IO_7") (pintype "bidirectional"))
    )
    (net (code "29") (name "/CP2102_RTS") (class "Default")
      (node (ref "IC2") (pin "24") (pinfunction "RTS_24") (pintype "output"))
      (node (ref "U1") (pin "3") (pinfunction "IO_3") (pintype "bidirectional"))
    )
    (net (code "30") (name "/CP2102_RXD") (class "Default")
      (node (ref "IC2") (pin "25") (pinfunction "RXD_25") (pintype "input"))
      (node (ref "U1") (pin "2") (pinfunction "IO_2") (pintype "bidirectional"))
    )
    (net (code "31") (name "/CP2102_TXD") (class "Default")
      (node (ref "IC2") (pin "26") (pinfunction "TXD_26") (pintype "output"))
      (node (ref "U1") (pin "1") (pinfunction "IO_1") (pintype "bidirectional"))
    )
    (net (code "32") (name "/CTS") (class "Default")
      (node (ref "U$4") (pin "10") (pinfunction "T2_IN_10") (pintype "bidirectional"))
      (node (ref "U1") (pin "113") (pinfunction "IO_113") (pintype "bidirectional"))
    )
    (net (code "33") (name "/DATA") (class "Default")
      (node (ref "AS") (pin "7") (pinfunction "7_7") (pintype "passive"))
      (node (ref "R26") (pin "1") (pinfunction "1_1") (pintype "passive"))
      (node (ref "U1") (pin "13") (pinfunction "IO_13") (pintype "bidirectional"))
    )
    (net (code "34") (name "/DCLK") (class "Default")
      (node (ref "AS") (pin "1") (pinfunction "1_1") (pintype "passive"))
      (node (ref "U$16") (pin "6") (pinfunction "SCLK_6") (pintype "bidirectional"))
      (node (ref "U1") (pin "12") (pinfunction "DCLK_12") (pintype "bidirectional"))
    )
    (net (code "35") (name "/DQ0") (class "Default")
      (node (ref "U$2") (pin "2") (pinfunction "DQ0_2") (pintype "bidirectional"))
      (node (ref "U1") (pin "43") (pinfunction "IO_43") (pintype "bidirectional"))
    )
    (net (code "36") (name "/DQ1") (class "Default")
      (node (ref "U$2") (pin "4") (pinfunction "DQ1_4") (pintype "bidirectional"))
      (node (ref "U1") (pin "44") (pinfunction "IO_44") (pintype "bidirectional"))
    )
    (net (code "37") (name "/DQ2") (class "Default")
      (node (ref "U$2") (pin "6") (pinfunction "DQ2_6") (pintype "bidirectional"))
      (node (ref "U1") (pin "46") (pinfunction "IO_46") (pintype "bidirectional"))
    )
    (net (code "38") (name "/DQ3") (class "Default")
      (node (ref "U$2") (pin "8") (pinfunction "DQ3_8") (pintype "bidirectional"))
      (node (ref "U1") (pin "49") (pinfunction "IO_49") (pintype "bidirectional"))
    )
    (net (code "39") (name "/DQ4") (class "Default")
      (node (ref "U$2") (pin "37") (pinfunction "DQ4_37") (pintype "bidirectional"))
      (node (ref "U1") (pin "50") (pinfunction "IO_50") (pintype "bidirectional"))
    )
    (net (code "40") (name "/DQ5") (class "Default")
      (node (ref "U$2") (pin "39") (pinfunction "DQ5_39") (pintype "bidirectional"))
      (node (ref "U1") (pin "51") (pinfunction "IO_51") (pintype "bidirectional"))
    )
    (net (code "41") (name "/DQ6") (class "Default")
      (node (ref "U$2") (pin "41") (pinfunction "DQ6_41") (pintype "bidirectional"))
      (node (ref "U1") (pin "52") (pinfunction "IO_52") (pintype "bidirectional"))
    )
    (net (code "42") (name "/DQ7") (class "Default")
      (node (ref "U$2") (pin "43") (pinfunction "DQ7_43") (pintype "bidirectional"))
      (node (ref "U1") (pin "53") (pinfunction "IO_53") (pintype "bidirectional"))
    )
    (net (code "43") (name "/DQM") (class "Default")
      (node (ref "U$2") (pin "33") (pinfunction "DQM_33") (pintype "bidirectional"))
      (node (ref "U1") (pin "54") (pinfunction "IO_54") (pintype "bidirectional"))
    )
    (net (code "44") (name "/FPGA_CLK") (class "Default")
      (node (ref "R27") (pin "2") (pinfunction "2_2") (pintype "passive"))
      (node (ref "U1") (pin "23") (pinfunction "CLK1_23") (pintype "bidirectional"))
    )
    (net (code "45") (name "/G0") (class "Default")
      (node (ref "R21") (pin "1") (pinfunction "1_1") (pintype "passive"))
      (node (ref "U1") (pin "105") (pinfunction "IO_105") (pintype "bidirectional"))
    )
    (net (code "46") (name "/G1") (class "Default")
      (node (ref "R20") (pin "1") (pinfunction "1_1") (pintype "passive"))
      (node (ref "U1") (pin "106") (pinfunction "IO_106") (pintype "bidirectional"))
    )
    (net (code "47") (name "/GND") (class "Default")
      (node (ref "AS") (pin "10") (pinfunction "10_10") (pintype "passive"))
      (node (ref "AS") (pin "2") (pinfunction "2_2") (pintype "passive"))
      (node (ref "AUDIO_OUT") (pin "SLEEVE") (pinfunction "SLEEVE_SLEEVE") (pintype "passive"))
      (node (ref "BUTTON_0") (pin "3") (pinfunction "3_3") (pintype "bidirectional"))
      (node (ref "BUTTON_1") (pin "3") (pinfunction "3_3") (pintype "bidirectional"))
      (node (ref "BUTTON_2") (pin "3") (pinfunction "3_3") (pintype "bidirectional"))
      (node (ref "BUTTON_3") (pin "3") (pinfunction "3_3") (pintype "bidirectional"))
      (node (ref "C1") (pin "-") (pinfunction "-_-") (pintype "passive"))
      (node (ref "C10") (pin "-") (pinfunction "-_-") (pintype "passive"))
      (node (ref "C11") (pin "-") (pinfunction "-_-") (pintype "passive"))
      (node (ref "C12") (pin "2") (pinfunction "2_2") (pintype "passive"))
      (node (ref "C13") (pin "2") (pinfunction "2_2") (pintype "passive"))
      (node (ref "C14") (pin "2") (pinfunction "2_2") (pintype "passive"))
      (node (ref "C15") (pin "2") (pinfunction "2_2") (pintype "passive"))
      (node (ref "C16") (pin "2") (pinfunction "2_2") (pintype "passive"))
      (node (ref "C17") (pin "2") (pinfunction "2_2") (pintype "passive"))
      (node (ref "C18") (pin "2") (pinfunction "2_2") (pintype "passive"))
      (node (ref "C2") (pin "-") (pinfunction "-_-") (pintype "passive"))
      (node (ref "C23") (pin "2") (pinfunction "2_2") (pintype "passive"))
      (node (ref "C27") (pin "2") (pinfunction "2_2") (pintype "passive"))
      (node (ref "C28") (pin "2") (pinfunction "2_2") (pintype "passive"))
      (node (ref "C29") (pin "2") (pinfunction "2_2") (pintype "passive"))
      (node (ref "C3") (pin "-") (pinfunction "-_-") (pintype "passive"))
      (node (ref "C30") (pin "2") (pinfunction "2_2") (pintype "passive"))
      (node (ref "C31") (pin "2") (pinfunction "2_2") (pintype "passive"))
      (node (ref "C32") (pin "2") (pinfunction "2_2") (pintype "passive"))
      (node (ref "C33") (pin "2") (pinfunction "2_2") (pintype "passive"))
      (node (ref "C34") (pin "2") (pinfunction "2_2") (pintype "passive"))
      (node (ref "C35") (pin "2") (pinfunction "2_2") (pintype "passive"))
      (node (ref "C36") (pin "2") (pinfunction "2_2") (pintype "passive"))
      (node (ref "C37") (pin "2") (pinfunction "2_2") (pintype "passive"))
      (node (ref "C38") (pin "2") (pinfunction "2_2") (pintype "passive"))
      (node (ref "C39") (pin "2") (pinfunction "2_2") (pintype "passive"))
      (node (ref "C4") (pin "2") (pinfunction "2_2") (pintype "passive"))
      (node (ref "C40") (pin "2") (pinfunction "2_2") (pintype "passive"))
      (node (ref "C41") (pin "2") (pinfunction "2_2") (pintype "passive"))
      (node (ref "C42") (pin "2") (pinfunction "2_2") (pintype "passive"))
      (node (ref "C43") (pin "2") (pinfunction "2_2") (pintype "passive"))
      (node (ref "C44") (pin "2") (pinfunction "2_2") (pintype "passive"))
      (node (ref "C45") (pin "2") (pinfunction "2_2") (pintype "passive"))
      (node (ref "C46") (pin "2") (pinfunction "2_2") (pintype "passive"))
      (node (ref "C47") (pin "2") (pinfunction "2_2") (pintype "passive"))
      (node (ref "C48") (pin "2") (pinfunction "2_2") (pintype "passive"))
      (node (ref "C49") (pin "2") (pinfunction "2_2") (pintype "passive"))
      (node (ref "C5") (pin "2") (pinfunction "2_2") (pintype "passive"))
      (node (ref "C50") (pin "2") (pinfunction "2_2") (pintype "passive"))
      (node (ref "C51") (pin "2") (pinfunction "2_2") (pintype "passive"))
      (node (ref "C52") (pin "2") (pinfunction "2_2") (pintype "passive"))
      (node (ref "C53") (pin "2") (pinfunction "2_2") (pintype "passive"))
      (node (ref "C54") (pin "2") (pinfunction "2_2") (pintype "passive"))
      (node (ref "C55") (pin "2") (pinfunction "2_2") (pintype "passive"))
      (node (ref "C56") (pin "2") (pinfunction "2_2") (pintype "passive"))
      (node (ref "C57") (pin "2") (pinfunction "2_2") (pintype "passive"))
      (node (ref "C58") (pin "2") (pinfunction "2_2") (pintype "passive"))
      (node (ref "C6") (pin "2") (pinfunction "2_2") (pintype "passive"))
      (node (ref "C7") (pin "2") (pinfunction "2_2") (pintype "passive"))
      (node (ref "C8") (pin "2") (pinfunction "2_2") (pintype "passive"))
      (node (ref "C9") (pin "2") (pinfunction "2_2") (pintype "passive"))
      (node (ref "IC2") (pin "1") (pinfunction "DCD_1") (pintype "input"))
      (node (ref "IC2") (pin "2") (pinfunction "RI_2") (pintype "input"))
      (node (ref "IC2") (pin "27") (pinfunction "DSR_27") (pintype "input"))
      (node (ref "IC2") (pin "3") (pinfunction "GND_3") (pintype "power_in"))
      (node (ref "IC2") (pin "EXP") (pinfunction "GND_EXP") (pintype "power_in"))
      (node (ref "IC2") (pin "M") (pinfunction "GND_M") (pintype "power_in"))
      (node (ref "J1") (pin "1") (pinfunction "1_1") (pintype "passive"))
      (node (ref "J1") (pin "2") (pinfunction "2_2") (pintype "passive"))
      (node (ref "JOYPAD1") (pin "3") (pinfunction "3_3") (pintype "passive"))
      (node (ref "JOYPAD1") (pin "S1") (pinfunction "SHIELD_S1") (pintype "bidirectional"))
      (node (ref "JOYPAD1") (pin "S2") (pinfunction "SHIELD_S2") (pintype "bidirectional"))
      (node (ref "JOYPAD1") (pin "S3") (pinfunction "SHIELD_S3") (pintype "bidirectional"))
      (node (ref "JOYPAD2") (pin "3") (pinfunction "3_3") (pintype "passive"))
      (node (ref "JOYPAD2") (pin "S1") (pinfunction "SHIELD_S1") (pintype "bidirectional"))
      (node (ref "JOYPAD2") (pin "S2") (pinfunction "SHIELD_S2") (pintype "bidirectional"))
      (node (ref "JOYPAD2") (pin "S3") (pinfunction "SHIELD_S3") (pintype "bidirectional"))
      (node (ref "JTAG") (pin "10") (pinfunction "10_10") (pintype "passive"))
      (node (ref "JTAG") (pin "2") (pinfunction "2_2") (pintype "passive"))
      (node (ref "MIC_OUT") (pin "SLEEVE") (pinfunction "SLEEVE_SLEEVE") (pintype "passive"))
      (node (ref "POWER") (pin "C") (pinfunction "C_C") (pintype "passive"))
      (node (ref "PS2") (pin "3") (pinfunction "3_3") (pintype "passive"))
      (node (ref "PS2") (pin "S1") (pinfunction "SHIELD_S1") (pintype "bidirectional"))
      (node (ref "PS2") (pin "S2") (pinfunction "SHIELD_S2") (pintype "bidirectional"))
      (node (ref "PS2") (pin "S3") (pinfunction "SHIELD_S3") (pintype "bidirectional"))
      (node (ref "R14") (pin "1") (pinfunction "1_1") (pintype "passive"))
      (node (ref "R15") (pin "1") (pinfunction "1_1") (pintype "passive"))
      (node (ref "R17") (pin "1") (pinfunction "1_1") (pintype "passive"))
      (node (ref "R28") (pin "1") (pinfunction "1_1") (pintype "passive"))
      (node (ref "R31") (pin "2") (pinfunction "2_2") (pintype "passive"))
      (node (ref "R41") (pin "1") (pinfunction "1_1") (pintype "passive"))
      (node (ref "R43") (pin "1") (pinfunction "1_1") (pintype "passive"))
      (node (ref "R5") (pin "1") (pinfunction "1_1") (pintype "passive"))
      (node (ref "R8") (pin "1") (pinfunction "1_1") (pintype "passive"))
      (node (ref "S1") (pin "3") (pinfunction "3_3") (pintype "bidirectional"))
      (node (ref "S1") (pin "4") (pinfunction "4_4") (pintype "bidirectional"))
      (node (ref "SERIAL") (pin "5") (pinfunction "5_5") (pintype "passive"))
      (node (ref "SERIAL") (pin "G1") (pinfunction "SHIELD_G1") (pintype "bidirectional"))
      (node (ref "SERIAL") (pin "G2") (pinfunction "SHIELD_G2") (pintype "bidirectional"))
      (node (ref "TAPE_IN") (pin "SLEEVE") (pinfunction "SLEEVE_SLEEVE") (pintype "passive"))
      (node (ref "TAPE_OUT") (pin "SLEEVE") (pinfunction "SLEEVE_SLEEVE") (pintype "passive"))
      (node (ref "U$1") (pin "3") (pinfunction "GND_3") (pintype "power_in"))
      (node (ref "U$12") (pin "2") (pinfunction "GND_2") (pintype "bidirectional"))
      (node (ref "U$13") (pin "2") (pinfunction "E_2") (pintype "passive"))
      (node (ref "U$14") (pin "2") (pinfunction "E_2") (pintype "passive"))
      (node (ref "U$15") (pin "2") (pinfunction "E_2") (pintype "passive"))
      (node (ref "U$16") (pin "4") (pinfunction "VSS_4") (pintype "bidirectional"))
      (node (ref "U$17") (pin "1") (pinfunction "NC_1") (pintype "bidirectional"))
      (node (ref "U$17") (pin "2") (pinfunction "A1_2") (pintype "bidirectional"))
      (node (ref "U$17") (pin "4") (pinfunction "VSS_4") (pintype "bidirectional"))
      (node (ref "U$17") (pin "7") (pinfunction "WP_7") (pintype "bidirectional"))
      (node (ref "U$18") (pin "2") (pinfunction "E_2") (pintype "passive"))
      (node (ref "U$19") (pin "2") (pinfunction "E_2") (pintype "passive"))
      (node (ref "U$2") (pin "23") (pinfunction "VSS1_23") (pintype "bidirectional"))
      (node (ref "U$2") (pin "3") (pinfunction "VSSQ0_3") (pintype "bidirectional"))
      (node (ref "U$2") (pin "38") (pinfunction "VSSQ3_38") (pintype "bidirectional"))
      (node (ref "U$2") (pin "42") (pinfunction "VSSQ2_42") (pintype "bidirectional"))
      (node (ref "U$2") (pin "44") (pinfunction "VSS0_44") (pintype "bidirectional"))
      (node (ref "U$2") (pin "7") (pinfunction "VSSQ1_7") (pintype "bidirectional"))
      (node (ref "U$20") (pin "2") (pinfunction "E_2") (pintype "passive"))
      (node (ref "U$21") (pin "2") (pinfunction "E_2") (pintype "passive"))
      (node (ref "U$3") (pin "A") (pinfunction "A_A") (pintype "passive"))
      (node (ref "U$4") (pin "15") (pinfunction "GND_15") (pintype "bidirectional"))
      (node (ref "U$5") (pin "1") (pinfunction "ADJ_1") (pintype "bidirectional"))
      (node (ref "U$6") (pin "P$1") (pinfunction "-_P$1") (pintype "passive"))
      (node (ref "U$7") (pin "1") (pinfunction "ADJ_1") (pintype "bidirectional"))
      (node (ref "U$8") (pin "1") (pinfunction "ADJ_1") (pintype "bidirectional"))
      (node (ref "U$9") (pin "1") (pinfunction "ADJ_1") (pintype "bidirectional"))
      (node (ref "U1") (pin "108") (pinfunction "GNDA2_108") (pintype "power_in"))
      (node (ref "U1") (pin "118") (pinfunction "GND_118") (pintype "power_in"))
      (node (ref "U1") (pin "123") (pinfunction "GND_123") (pintype "power_in"))
      (node (ref "U1") (pin "131") (pinfunction "GND_131") (pintype "power_in"))
      (node (ref "U1") (pin "140") (pinfunction "GND_140") (pintype "power_in"))
      (node (ref "U1") (pin "145") (pinfunction "EXP_145") (pintype "power_in"))
      (node (ref "U1") (pin "19") (pinfunction "GND_19") (pintype "power_in"))
      (node (ref "U1") (pin "22") (pinfunction "GND_22") (pintype "power_in"))
      (node (ref "U1") (pin "24") (pinfunction "CLK2_24") (pintype "bidirectional"))
      (node (ref "U1") (pin "27") (pinfunction "GND_27") (pintype "power_in"))
      (node (ref "U1") (pin "36") (pinfunction "GNDA1_36") (pintype "power_in"))
      (node (ref "U1") (pin "4") (pinfunction "GND_4") (pintype "power_in"))
      (node (ref "U1") (pin "41") (pinfunction "GND_41") (pintype "power_in"))
      (node (ref "U1") (pin "48") (pinfunction "GND_48") (pintype "power_in"))
      (node (ref "U1") (pin "57") (pinfunction "GND_57") (pintype "power_in"))
      (node (ref "U1") (pin "63") (pinfunction "GND_63") (pintype "power_in"))
      (node (ref "U1") (pin "79") (pinfunction "GND_79") (pintype "power_in"))
      (node (ref "U1") (pin "82") (pinfunction "GND_82") (pintype "power_in"))
      (node (ref "U1") (pin "88") (pinfunction "CLK7_88") (pintype "bidirectional"))
      (node (ref "U1") (pin "89") (pinfunction "CLK6_89") (pintype "bidirectional"))
      (node (ref "U1") (pin "90") (pinfunction "CLK5_90") (pintype "bidirectional"))
      (node (ref "U1") (pin "91") (pinfunction "CLK4_91") (pintype "bidirectional"))
      (node (ref "U1") (pin "94") (pinfunction "MSEL0_94") (pintype "bidirectional"))
      (node (ref "U1") (pin "95") (pinfunction "GND_95") (pintype "power_in"))
      (node (ref "U1") (pin "97") (pinfunction "MSEL2_97") (pintype "bidirectional"))
      (node (ref "VGA") (pin "10") (pinfunction "10_10") (pintype "passive"))
      (node (ref "VGA") (pin "5") (pinfunction "5_5") (pintype "passive"))
      (node (ref "VGA") (pin "6") (pinfunction "6_6") (pintype "passive"))
      (node (ref "VGA") (pin "7") (pinfunction "7_7") (pintype "passive"))
      (node (ref "VGA") (pin "8") (pinfunction "8_8") (pintype "passive"))
      (node (ref "VGA") (pin "S1") (pinfunction "SHIELD_S1") (pintype "bidirectional"))
      (node (ref "VGA") (pin "S2") (pinfunction "SHIELD_S2") (pintype "bidirectional"))
      (node (ref "X1") (pin "4") (pinfunction "4_4") (pintype "passive"))
      (node (ref "X1") (pin "S1") (pinfunction "S1_S1") (pintype "passive"))
      (node (ref "X1") (pin "S2") (pinfunction "S2_S2") (pintype "passive"))
    )
    (net (code "48") (name "/HSYNC") (class "Default")
      (node (ref "R18") (pin "2") (pinfunction "2_2") (pintype "passive"))
      (node (ref "U1") (pin "100") (pinfunction "IO_100") (pintype "bidirectional"))
    )
    (net (code "49") (name "/I2C_SCL") (class "Default")
      (node (ref "U$17") (pin "6") (pinfunction "SCL_6") (pintype "bidirectional"))
      (node (ref "U1") (pin "143") (pinfunction "IO_143") (pintype "bidirectional"))
    )
    (net (code "50") (name "/I2C_SDA") (class "Default")
      (node (ref "U$17") (pin "5") (pinfunction "SDA_5") (pintype "bidirectional"))
      (node (ref "U1") (pin "144") (pinfunction "IO_144") (pintype "bidirectional"))
    )
    (net (code "51") (name "/JP1_CLK") (class "Default")
      (node (ref "JOYPAD1") (pin "5") (pinfunction "5_5") (pintype "passive"))
      (node (ref "R35") (pin "2") (pinfunction "2_2") (pintype "passive"))
      (node (ref "U$18") (pin "3") (pinfunction "C_3") (pintype "passive"))
    )
    (net (code "52") (name "/JP1_CLK_Q") (class "Default")
      (node (ref "R39") (pin "1") (pinfunction "1_1") (pintype "passive"))
      (node (ref "U1") (pin "87") (pinfunction "IO_87") (pintype "bidirectional"))
    )
    (net (code "53") (name "/JP1_DATA") (class "Default")
      (node (ref "JOYPAD1") (pin "1") (pinfunction "1_1") (pintype "passive"))
      (node (ref "R40") (pin "2") (pinfunction "2_2") (pintype "passive"))
    )
    (net (code "54") (name "/JP1_DATA_D") (class "Default")
      (node (ref "R40") (pin "1") (pinfunction "1_1") (pintype "passive"))
      (node (ref "R41") (pin "2") (pinfunction "2_2") (pintype "passive"))
      (node (ref "U1") (pin "85") (pinfunction "IO_85") (pintype "bidirectional"))
    )
    (net (code "55") (name "/JP1_LATCH") (class "Default")
      (node (ref "JOYPAD1") (pin "6") (pinfunction "6_6") (pintype "passive"))
      (node (ref "R34") (pin "2") (pinfunction "2_2") (pintype "passive"))
      (node (ref "U$19") (pin "3") (pinfunction "C_3") (pintype "passive"))
    )
    (net (code "56") (name "/JP1_LATCH_Q") (class "Default")
      (node (ref "R38") (pin "1") (pinfunction "1_1") (pintype "passive"))
      (node (ref "U1") (pin "86") (pinfunction "IO_86") (pintype "bidirectional"))
    )
    (net (code "57") (name "/JP2_CLK") (class "Default")
      (node (ref "JOYPAD2") (pin "5") (pinfunction "5_5") (pintype "passive"))
      (node (ref "R33") (pin "2") (pinfunction "2_2") (pintype "passive"))
      (node (ref "U$20") (pin "3") (pinfunction "C_3") (pintype "passive"))
    )
    (net (code "58") (name "/JP2_CLK_Q") (class "Default")
      (node (ref "R37") (pin "1") (pinfunction "1_1") (pintype "passive"))
      (node (ref "U1") (pin "99") (pinfunction "IO_99") (pintype "bidirectional"))
    )
    (net (code "59") (name "/JP2_DATA") (class "Default")
      (node (ref "JOYPAD2") (pin "1") (pinfunction "1_1") (pintype "passive"))
      (node (ref "R42") (pin "2") (pinfunction "2_2") (pintype "passive"))
    )
    (net (code "60") (name "/JP2_DATA_D") (class "Default")
      (node (ref "R42") (pin "1") (pinfunction "1_1") (pintype "passive"))
      (node (ref "R43") (pin "2") (pinfunction "2_2") (pintype "passive"))
      (node (ref "U1") (pin "84") (pinfunction "IO_84") (pintype "bidirectional"))
    )
    (net (code "61") (name "/JP2_LATCH") (class "Default")
      (node (ref "JOYPAD2") (pin "6") (pinfunction "6_6") (pintype "passive"))
      (node (ref "R32") (pin "2") (pinfunction "2_2") (pintype "passive"))
      (node (ref "U$21") (pin "3") (pinfunction "C_3") (pintype "passive"))
    )
    (net (code "62") (name "/JP2_LATCH_Q") (class "Default")
      (node (ref "R36") (pin "1") (pinfunction "1_1") (pintype "passive"))
      (node (ref "U1") (pin "98") (pinfunction "IO_98") (pintype "bidirectional"))
    )
    (net (code "63") (name "/LED_0") (class "Default")
      (node (ref "LED_0") (pin "C") (pinfunction "C_C") (pintype "passive"))
      (node (ref "U1") (pin "33") (pinfunction "IO_33") (pintype "bidirectional"))
    )
    (net (code "64") (name "/LED_1") (class "Default")
      (node (ref "LED_1") (pin "C") (pinfunction "C_C") (pintype "passive"))
      (node (ref "U1") (pin "32") (pinfunction "IO_32") (pintype "bidirectional"))
    )
    (net (code "65") (name "/LED_2") (class "Default")
      (node (ref "LED_2") (pin "C") (pinfunction "C_C") (pintype "passive"))
      (node (ref "U1") (pin "31") (pinfunction "IO_31") (pintype "bidirectional"))
    )
    (net (code "66") (name "/LED_3") (class "Default")
      (node (ref "LED_3") (pin "C") (pinfunction "C_C") (pintype "passive"))
      (node (ref "U1") (pin "30") (pinfunction "IO_30") (pintype "bidirectional"))
    )
    (net (code "67") (name "/PS2_CLK") (class "Default")
      (node (ref "PS2") (pin "5") (pinfunction "5_5") (pintype "passive"))
      (node (ref "R11") (pin "2") (pinfunction "2_2") (pintype "passive"))
      (node (ref "R13") (pin "2") (pinfunction "2_2") (pintype "passive"))
      (node (ref "U$14") (pin "3") (pinfunction "C_3") (pintype "passive"))
    )
    (net (code "68") (name "/PS2_CLK_D") (class "Default")
      (node (ref "R13") (pin "1") (pinfunction "1_1") (pintype "passive"))
      (node (ref "R15") (pin "2") (pinfunction "2_2") (pintype "passive"))
      (node (ref "U1") (pin "120") (pinfunction "IO_120") (pintype "bidirectional"))
    )
    (net (code "69") (name "/PS2_CLK_Q") (class "Default")
      (node (ref "R3") (pin "1") (pinfunction "1_1") (pintype "passive"))
      (node (ref "U1") (pin "124") (pinfunction "IO_124") (pintype "bidirectional"))
    )
    (net (code "70") (name "/PS2_DATA") (class "Default")
      (node (ref "PS2") (pin "1") (pinfunction "1_1") (pintype "passive"))
      (node (ref "R10") (pin "2") (pinfunction "2_2") (pintype "passive"))
      (node (ref "R12") (pin "2") (pinfunction "2_2") (pintype "passive"))
      (node (ref "U$13") (pin "3") (pinfunction "C_3") (pintype "passive"))
    )
    (net (code "71") (name "/PS2_DATA_D") (class "Default")
      (node (ref "R12") (pin "1") (pinfunction "1_1") (pintype "passive"))
      (node (ref "R14") (pin "2") (pinfunction "2_2") (pintype "passive"))
      (node (ref "U1") (pin "119") (pinfunction "IO_119") (pintype "bidirectional"))
    )
    (net (code "72") (name "/PS2_DATA_Q") (class "Default")
      (node (ref "R2") (pin "1") (pinfunction "1_1") (pintype "passive"))
      (node (ref "U1") (pin "121") (pinfunction "IO_121") (pintype "bidirectional"))
    )
    (net (code "73") (name "/R0") (class "Default")
      (node (ref "R24") (pin "1") (pinfunction "1_1") (pintype "passive"))
      (node (ref "U1") (pin "110") (pinfunction "IO_110") (pintype "bidirectional"))
    )
    (net (code "74") (name "/R1") (class "Default")
      (node (ref "R25") (pin "1") (pinfunction "1_1") (pintype "passive"))
      (node (ref "U1") (pin "111") (pinfunction "IO_111") (pintype "bidirectional"))
    )
    (net (code "75") (name "/RESET") (class "Default")
      (node (ref "C57") (pin "1") (pinfunction "1_1") (pintype "passive"))
      (node (ref "R44") (pin "1") (pinfunction "1_1") (pintype "passive"))
      (node (ref "S1") (pin "2") (pinfunction "2_2") (pintype "bidirectional"))
      (node (ref "U1") (pin "25") (pinfunction "CLK3_25") (pintype "bidirectional"))
    )
    (net (code "76") (name "/RTS") (class "Default")
      (node (ref "U$4") (pin "9") (pinfunction "R2_OUT_9") (pintype "bidirectional"))
      (node (ref "U1") (pin "112") (pinfunction "IO_112") (pintype "bidirectional"))
    )
    (net (code "77") (name "/RW") (class "Default")
      (node (ref "U$2") (pin "12") (pinfunction "~{W}_12") (pintype "bidirectional"))
      (node (ref "U1") (pin "69") (pinfunction "IO_69") (pintype "bidirectional"))
    )
    (net (code "78") (name "/RXD") (class "Default")
      (node (ref "U$4") (pin "12") (pinfunction "R1_OUT_12") (pintype "bidirectional"))
      (node (ref "U1") (pin "115") (pinfunction "IO_115") (pintype "bidirectional"))
    )
    (net (code "79") (name "/SDRAM_CLK") (class "Default")
      (node (ref "U$2") (pin "32") (pinfunction "CLK_32") (pintype "bidirectional"))
      (node (ref "U1") (pin "55") (pinfunction "IO_55") (pintype "bidirectional"))
    )
    (net (code "80") (name "/TAPE_IN") (class "Default")
      (node (ref "U$1") (pin "4") (pinfunction "Y_4") (pintype "output"))
      (node (ref "U1") (pin "127") (pinfunction "IO_127") (pintype "bidirectional"))
    )
    (net (code "81") (name "/TAPE_OUT") (class "Default")
      (node (ref "R4") (pin "1") (pinfunction "1_1") (pintype "passive"))
      (node (ref "R9") (pin "1") (pinfunction "1_1") (pintype "passive"))
      (node (ref "U1") (pin "125") (pinfunction "IO_125") (pintype "bidirectional"))
    )
    (net (code "82") (name "/TCK") (class "Default")
      (node (ref "JTAG") (pin "1") (pinfunction "1_1") (pintype "passive"))
      (node (ref "R28") (pin "2") (pinfunction "2_2") (pintype "passive"))
      (node (ref "U1") (pin "16") (pinfunction "TCK_16") (pintype "bidirectional"))
    )
    (net (code "83") (name "/TDI") (class "Default")
      (node (ref "JTAG") (pin "9") (pinfunction "9_9") (pintype "passive"))
      (node (ref "R30") (pin "2") (pinfunction "2_2") (pintype "passive"))
      (node (ref "U1") (pin "15") (pinfunction "TDI_15") (pintype "bidirectional"))
    )
    (net (code "84") (name "/TDO") (class "Default")
      (node (ref "JTAG") (pin "3") (pinfunction "3_3") (pintype "passive"))
      (node (ref "U1") (pin "20") (pinfunction "TDO_20") (pintype "bidirectional"))
    )
    (net (code "85") (name "/TMS") (class "Default")
      (node (ref "JTAG") (pin "5") (pinfunction "5_5") (pintype "passive"))
      (node (ref "R29") (pin "2") (pinfunction "2_2") (pintype "passive"))
      (node (ref "U1") (pin "18") (pinfunction "TMS_18") (pintype "bidirectional"))
    )
    (net (code "86") (name "/TXD") (class "Default")
      (node (ref "U$4") (pin "11") (pinfunction "T1_IN_11") (pintype "bidirectional"))
      (node (ref "U1") (pin "114") (pinfunction "IO_114") (pintype "bidirectional"))
    )
    (net (code "87") (name "/VSYNC") (class "Default")
      (node (ref "R19") (pin "2") (pinfunction "2_2") (pintype "passive"))
      (node (ref "U1") (pin "101") (pinfunction "IO_101") (pintype "bidirectional"))
    )
    (net (code "88") (name "/~{CAS}") (class "Default")
      (node (ref "U$2") (pin "13") (pinfunction "~{CAS}_13") (pintype "bidirectional"))
      (node (ref "U1") (pin "70") (pinfunction "IO_70") (pintype "bidirectional"))
    )
    (net (code "89") (name "/~{CE}") (class "Default")
      (node (ref "AS") (pin "6") (pinfunction "6_6") (pintype "passive"))
      (node (ref "R31") (pin "1") (pinfunction "1_1") (pintype "passive"))
      (node (ref "U1") (pin "21") (pinfunction "NCE_21") (pintype "bidirectional"))
    )
    (net (code "90") (name "/~{CONFIG}") (class "Default")
      (node (ref "AS") (pin "5") (pinfunction "5_5") (pintype "passive"))
      (node (ref "R46") (pin "2") (pinfunction "2_2") (pintype "passive"))
      (node (ref "U1") (pin "14") (pinfunction "NCONFIG_14") (pintype "bidirectional"))
    )
    (net (code "91") (name "/~{CSO}") (class "Default")
      (node (ref "AS") (pin "8") (pinfunction "8_8") (pintype "passive"))
      (node (ref "U$16") (pin "1") (pinfunction "~{CS}_1") (pintype "bidirectional"))
      (node (ref "U1") (pin "8") (pinfunction "IO_8") (pintype "bidirectional"))
    )
    (net (code "92") (name "/~{CS}") (class "Default")
      (node (ref "U$2") (pin "15") (pinfunction "~{CS}_15") (pintype "bidirectional"))
      (node (ref "U1") (pin "72") (pinfunction "IO_72") (pintype "bidirectional"))
    )
    (net (code "93") (name "/~{RAS}") (class "Default")
      (node (ref "U$2") (pin "14") (pinfunction "~{RAS}_14") (pintype "bidirectional"))
      (node (ref "U1") (pin "71") (pinfunction "IO_71") (pintype "bidirectional"))
    )
    (net (code "94") (name "Net-(AUDIO_OUT-PadRING)") (class "Default")
      (node (ref "AUDIO_OUT") (pin "RING") (pinfunction "RING_RING") (pintype "passive"))
      (node (ref "AUDIO_OUT") (pin "TIP") (pinfunction "TIP_TIP") (pintype "passive"))
      (node (ref "C21") (pin "1") (pinfunction "1_1") (pintype "passive"))
      (node (ref "R5") (pin "2") (pinfunction "2_2") (pintype "passive"))
    )
    (net (code "95") (name "Net-(C19-Pad2)") (class "Default")
      (node (ref "C19") (pin "2") (pinfunction "2_2") (pintype "passive"))
      (node (ref "R16") (pin "2") (pinfunction "2_2") (pintype "passive"))
    )
    (net (code "96") (name "Net-(C20-Pad1)") (class "Default")
      (node (ref "C20") (pin "1") (pinfunction "1_1") (pintype "passive"))
      (node (ref "TAPE_OUT") (pin "RING") (pinfunction "RING_RING") (pintype "passive"))
      (node (ref "TAPE_OUT") (pin "TIP") (pinfunction "TIP_TIP") (pintype "passive"))
    )
    (net (code "97") (name "Net-(C21-Pad2)") (class "Default")
      (node (ref "C21") (pin "2") (pinfunction "2_2") (pintype "passive"))
      (node (ref "R6") (pin "2") (pinfunction "2_2") (pintype "passive"))
    )
    (net (code "98") (name "Net-(C22-Pad1)") (class "Default")
      (node (ref "C22") (pin "1") (pinfunction "1_1") (pintype "passive"))
      (node (ref "MIC_OUT") (pin "TIP") (pinfunction "TIP_TIP") (pintype "passive"))
      (node (ref "R8") (pin "2") (pinfunction "2_2") (pintype "passive"))
    )
    (net (code "99") (name "Net-(C22-Pad2)") (class "Default")
      (node (ref "C22") (pin "2") (pinfunction "2_2") (pintype "passive"))
      (node (ref "R9") (pin "2") (pinfunction "2_2") (pintype "passive"))
    )
    (net (code "100") (name "Net-(D1-PadA)") (class "Default")
      (node (ref "D1") (pin "A") (pinfunction "A_A") (pintype "passive"))
      (node (ref "J1") (pin "3") (pinfunction "3_3") (pintype "passive"))
    )
    (net (code "101") (name "Net-(IC2-D+)") (class "Default")
      (node (ref "IC2") (pin "4") (pinfunction "D+_4") (pintype "bidirectional"))
      (node (ref "X1") (pin "3") (pinfunction "3_3") (pintype "passive"))
    )
    (net (code "102") (name "Net-(IC2-D-)") (class "Default")
      (node (ref "IC2") (pin "5") (pinfunction "D-_5") (pintype "bidirectional"))
      (node (ref "X1") (pin "2") (pinfunction "2_2") (pintype "passive"))
    )
    (net (code "103") (name "Net-(IC2-REGIN)") (class "Default")
      (node (ref "C13") (pin "1") (pinfunction "1_1") (pintype "passive"))
      (node (ref "D2") (pin "A") (pinfunction "A_A") (pintype "passive"))
      (node (ref "IC2") (pin "7") (pinfunction "REGIN_7") (pintype "passive"))
      (node (ref "IC2") (pin "8") (pinfunction "VBUS_8") (pintype "input"))
      (node (ref "X1") (pin "1") (pinfunction "1_1") (pintype "passive"))
    )
    (net (code "104") (name "Net-(IC2-VDD)") (class "Default")
      (node (ref "C12") (pin "1") (pinfunction "1_1") (pintype "passive"))
      (node (ref "C14") (pin "1") (pinfunction "1_1") (pintype "passive"))
      (node (ref "IC2") (pin "6") (pinfunction "VDD_6") (pintype "power_in"))
      (node (ref "R1") (pin "1") (pinfunction "1_1") (pintype "passive"))
    )
    (net (code "105") (name "Net-(IC2-~{RST})") (class "Default")
      (node (ref "IC2") (pin "9") (pinfunction "~{RST}_9") (pintype "bidirectional"))
      (node (ref "R1") (pin "2") (pinfunction "2_2") (pintype "passive"))
    )
    (net (code "106") (name "Net-(LED_0-PadA)") (class "Default")
      (node (ref "LED_0") (pin "A") (pinfunction "A_A") (pintype "passive"))
      (node (ref "R55") (pin "2") (pinfunction "2_2") (pintype "passive"))
    )
    (net (code "107") (name "Net-(LED_1-PadA)") (class "Default")
      (node (ref "LED_1") (pin "A") (pinfunction "A_A") (pintype "passive"))
      (node (ref "R54") (pin "2") (pinfunction "2_2") (pintype "passive"))
    )
    (net (code "108") (name "Net-(LED_2-PadA)") (class "Default")
      (node (ref "LED_2") (pin "A") (pinfunction "A_A") (pintype "passive"))
      (node (ref "R53") (pin "2") (pinfunction "2_2") (pintype "passive"))
    )
    (net (code "109") (name "Net-(LED_3-PadA)") (class "Default")
      (node (ref "LED_3") (pin "A") (pinfunction "A_A") (pintype "passive"))
      (node (ref "R52") (pin "2") (pinfunction "2_2") (pintype "passive"))
    )
    (net (code "110") (name "Net-(POWER-PadA)") (class "Default")
      (node (ref "POWER") (pin "A") (pinfunction "A_A") (pintype "passive"))
      (node (ref "R56") (pin "2") (pinfunction "2_2") (pintype "passive"))
    )
    (net (code "111") (name "Net-(R18-Pad1)") (class "Default")
      (node (ref "R18") (pin "1") (pinfunction "1_1") (pintype "passive"))
      (node (ref "VGA") (pin "13") (pinfunction "13_13") (pintype "passive"))
    )
    (net (code "112") (name "Net-(R19-Pad1)") (class "Default")
      (node (ref "R19") (pin "1") (pinfunction "1_1") (pintype "passive"))
      (node (ref "VGA") (pin "14") (pinfunction "14_14") (pintype "passive"))
    )
    (net (code "113") (name "Net-(R20-Pad2)") (class "Default")
      (node (ref "R20") (pin "2") (pinfunction "2_2") (pintype "passive"))
      (node (ref "R21") (pin "2") (pinfunction "2_2") (pintype "passive"))
      (node (ref "VGA") (pin "2") (pinfunction "2_2") (pintype "passive"))
    )
    (net (code "114") (name "Net-(R22-Pad2)") (class "Default")
      (node (ref "R22") (pin "2") (pinfunction "2_2") (pintype "passive"))
      (node (ref "R23") (pin "2") (pinfunction "2_2") (pintype "passive"))
      (node (ref "VGA") (pin "3") (pinfunction "3_3") (pintype "passive"))
    )
    (net (code "115") (name "Net-(R24-Pad2)") (class "Default")
      (node (ref "R24") (pin "2") (pinfunction "2_2") (pintype "passive"))
      (node (ref "R25") (pin "2") (pinfunction "2_2") (pintype "passive"))
      (node (ref "VGA") (pin "1") (pinfunction "1_1") (pintype "passive"))
    )
    (net (code "116") (name "Net-(U$1-A)") (class "Default")
      (node (ref "C19") (pin "1") (pinfunction "1_1") (pintype "passive"))
      (node (ref "U$1") (pin "2") (pinfunction "A_2") (pintype "input"))
      (node (ref "U$3") (pin "C") (pinfunction "C_C") (pintype "passive"))
    )
    (net (code "117") (name "Net-(U$4-C1+)") (class "Default")
      (node (ref "C25") (pin "1") (pinfunction "1_1") (pintype "passive"))
      (node (ref "U$4") (pin "1") (pinfunction "C1+_1") (pintype "bidirectional"))
    )
    (net (code "118") (name "Net-(U$4-C1-)") (class "Default")
      (node (ref "C25") (pin "2") (pinfunction "2_2") (pintype "passive"))
      (node (ref "U$4") (pin "3") (pinfunction "C1-_3") (pintype "bidirectional"))
    )
    (net (code "119") (name "Net-(U$4-C2+)") (class "Default")
      (node (ref "C26") (pin "1") (pinfunction "1_1") (pintype "passive"))
      (node (ref "U$4") (pin "4") (pinfunction "C2+_4") (pintype "bidirectional"))
    )
    (net (code "120") (name "Net-(U$4-C2-)") (class "Default")
      (node (ref "C26") (pin "2") (pinfunction "2_2") (pintype "passive"))
      (node (ref "U$4") (pin "5") (pinfunction "C2-_5") (pintype "bidirectional"))
    )
    (net (code "121") (name "Net-(U$4-R1_IN)") (class "Default")
      (node (ref "SERIAL") (pin "3") (pinfunction "3_3") (pintype "passive"))
      (node (ref "U$4") (pin "13") (pinfunction "R1_IN_13") (pintype "bidirectional"))
    )
    (net (code "122") (name "Net-(U$4-R2_IN)") (class "Default")
      (node (ref "SERIAL") (pin "8") (pinfunction "8_8") (pintype "passive"))
      (node (ref "U$4") (pin "8") (pinfunction "R2_IN_8") (pintype "bidirectional"))
    )
    (net (code "123") (name "Net-(U$4-T1_OUT)") (class "Default")
      (node (ref "SERIAL") (pin "2") (pinfunction "2_2") (pintype "passive"))
      (node (ref "U$4") (pin "14") (pinfunction "T1_OUT_14") (pintype "bidirectional"))
    )
    (net (code "124") (name "Net-(U$4-T2_OUT)") (class "Default")
      (node (ref "SERIAL") (pin "7") (pinfunction "7_7") (pintype "passive"))
      (node (ref "U$4") (pin "7") (pinfunction "T2_OUT_7") (pintype "bidirectional"))
    )
    (net (code "125") (name "Net-(U$4-V+)") (class "Default")
      (node (ref "C24") (pin "2") (pinfunction "2_2") (pintype "passive"))
      (node (ref "U$4") (pin "2") (pinfunction "V+_2") (pintype "bidirectional"))
    )
    (net (code "126") (name "Net-(U$4-V-)") (class "Default")
      (node (ref "C23") (pin "1") (pinfunction "1_1") (pintype "passive"))
      (node (ref "U$4") (pin "6") (pinfunction "V-_6") (pintype "bidirectional"))
    )
    (net (code "127") (name "Net-(U$5-IN)") (class "Default")
      (node (ref "C4") (pin "1") (pinfunction "1_1") (pintype "passive"))
      (node (ref "D1") (pin "C") (pinfunction "C_C") (pintype "passive"))
      (node (ref "U$5") (pin "3") (pinfunction "IN_3") (pintype "bidirectional"))
      (node (ref "U$6") (pin "P$2") (pinfunction "+_P$2") (pintype "passive"))
    )
    (net (code "128") (name "Net-(U$12-OUT)") (class "Default")
      (node (ref "R27") (pin "1") (pinfunction "1_1") (pintype "passive"))
      (node (ref "U$12") (pin "3") (pinfunction "OUT_3") (pintype "bidirectional"))
    )
    (net (code "129") (name "Net-(U$13-B)") (class "Default")
      (node (ref "R2") (pin "2") (pinfunction "2_2") (pintype "passive"))
      (node (ref "U$13") (pin "1") (pinfunction "B_1") (pintype "passive"))
    )
    (net (code "130") (name "Net-(U$14-B)") (class "Default")
      (node (ref "R3") (pin "2") (pinfunction "2_2") (pintype "passive"))
      (node (ref "U$14") (pin "1") (pinfunction "B_1") (pintype "passive"))
    )
    (net (code "131") (name "Net-(U$15-B)") (class "Default")
      (node (ref "R4") (pin "2") (pinfunction "2_2") (pintype "passive"))
      (node (ref "U$15") (pin "1") (pinfunction "B_1") (pintype "passive"))
    )
    (net (code "132") (name "Net-(U$15-C)") (class "Default")
      (node (ref "C20") (pin "2") (pinfunction "2_2") (pintype "passive"))
      (node (ref "R7") (pin "2") (pinfunction "2_2") (pintype "passive"))
      (node (ref "U$15") (pin "3") (pinfunction "C_3") (pintype "passive"))
    )
    (net (code "133") (name "Net-(U$16-SO)") (class "Default")
      (node (ref "R26") (pin "2") (pinfunction "2_2") (pintype "passive"))
      (node (ref "U$16") (pin "2") (pinfunction "SO_2") (pintype "bidirectional"))
    )
    (net (code "134") (name "Net-(U$18-B)") (class "Default")
      (node (ref "R39") (pin "2") (pinfunction "2_2") (pintype "passive"))
      (node (ref "U$18") (pin "1") (pinfunction "B_1") (pintype "passive"))
    )
    (net (code "135") (name "Net-(U$19-B)") (class "Default")
      (node (ref "R38") (pin "2") (pinfunction "2_2") (pintype "passive"))
      (node (ref "U$19") (pin "1") (pinfunction "B_1") (pintype "passive"))
    )
    (net (code "136") (name "Net-(U$20-B)") (class "Default")
      (node (ref "R37") (pin "2") (pinfunction "2_2") (pintype "passive"))
      (node (ref "U$20") (pin "1") (pinfunction "B_1") (pintype "passive"))
    )
    (net (code "137") (name "Net-(U$21-B)") (class "Default")
      (node (ref "R36") (pin "2") (pinfunction "2_2") (pintype "passive"))
      (node (ref "U$21") (pin "1") (pinfunction "B_1") (pintype "passive"))
    )
    (net (code "138") (name "Net-(U1-NSTATUS)") (class "Default")
      (node (ref "R45") (pin "2") (pinfunction "2_2") (pintype "passive"))
      (node (ref "U1") (pin "9") (pinfunction "NSTATUS_9") (pintype "bidirectional"))
    )
    (net (code "139") (name "Net-(U1-VCCD_PLL1)") (class "Default")
      (node (ref "C17") (pin "1") (pinfunction "1_1") (pintype "passive"))
      (node (ref "U$10") (pin "1") (pinfunction "1_1") (pintype "passive"))
      (node (ref "U1") (pin "37") (pinfunction "VCCD_PLL1_37") (pintype "power_in"))
    )
    (net (code "140") (name "Net-(U1-VCCD_PLL2)") (class "Default")
      (node (ref "C18") (pin "1") (pinfunction "1_1") (pintype "passive"))
      (node (ref "U$11") (pin "1") (pinfunction "1_1") (pintype "passive"))
      (node (ref "U1") (pin "109") (pinfunction "VCCD_PLL2_109") (pintype "power_in"))
    )
    (net (code "141") (name "unconnected-(AUDIO_OUT-PadRING_SWITCH)") (class "Default")
      (node (ref "AUDIO_OUT") (pin "RING_SWITCH") (pinfunction "RING_SWITCH_RING_SWITCH") (pintype "passive"))
    )
    (net (code "142") (name "unconnected-(AUDIO_OUT-PadTIP_SWITCH)") (class "Default")
      (node (ref "AUDIO_OUT") (pin "TIP_SWITCH") (pinfunction "TIP_SWITCH_TIP_SWITCH") (pintype "passive"))
    )
    (net (code "143") (name "unconnected-(BUTTON_0-Pad1)") (class "Default")
      (node (ref "BUTTON_0") (pin "1") (pinfunction "1_1") (pintype "bidirectional"))
    )
    (net (code "144") (name "unconnected-(BUTTON_0-Pad4)") (class "Default")
      (node (ref "BUTTON_0") (pin "4") (pinfunction "4_4") (pintype "bidirectional"))
    )
    (net (code "145") (name "unconnected-(BUTTON_1-Pad1)") (class "Default")
      (node (ref "BUTTON_1") (pin "1") (pinfunction "1_1") (pintype "bidirectional"))
    )
    (net (code "146") (name "unconnected-(BUTTON_1-Pad4)") (class "Default")
      (node (ref "BUTTON_1") (pin "4") (pinfunction "4_4") (pintype "bidirectional"))
    )
    (net (code "147") (name "unconnected-(BUTTON_2-Pad1)") (class "Default")
      (node (ref "BUTTON_2") (pin "1") (pinfunction "1_1") (pintype "bidirectional"))
    )
    (net (code "148") (name "unconnected-(BUTTON_2-Pad4)") (class "Default")
      (node (ref "BUTTON_2") (pin "4") (pinfunction "4_4") (pintype "bidirectional"))
    )
    (net (code "149") (name "unconnected-(BUTTON_3-Pad1)") (class "Default")
      (node (ref "BUTTON_3") (pin "1") (pinfunction "1_1") (pintype "bidirectional"))
    )
    (net (code "150") (name "unconnected-(BUTTON_3-Pad4)") (class "Default")
      (node (ref "BUTTON_3") (pin "4") (pinfunction "4_4") (pintype "bidirectional"))
    )
    (net (code "151") (name "unconnected-(H1-MOUNT-PadB3,0)") (class "Default")
      (node (ref "H1") (pin "B3,0") (pinfunction "MOUNT_B3,0") (pintype "passive"))
    )
    (net (code "152") (name "unconnected-(H2-MOUNT-PadB3,0)") (class "Default")
      (node (ref "H2") (pin "B3,0") (pinfunction "MOUNT_B3,0") (pintype "passive"))
    )
    (net (code "153") (name "unconnected-(H3-MOUNT-PadB3,0)") (class "Default")
      (node (ref "H3") (pin "B3,0") (pinfunction "MOUNT_B3,0") (pintype "passive"))
    )
    (net (code "154") (name "unconnected-(H4-MOUNT-PadB3,0)") (class "Default")
      (node (ref "H4") (pin "B3,0") (pinfunction "MOUNT_B3,0") (pintype "passive"))
    )
    (net (code "155") (name "unconnected-(IC2-DTR-Pad28)") (class "Default")
      (node (ref "IC2") (pin "28") (pinfunction "DTR_28") (pintype "output"))
    )
    (net (code "156") (name "unconnected-(IC2-SUSPEND-Pad12)") (class "Default")
      (node (ref "IC2") (pin "12") (pinfunction "SUSPEND_12") (pintype "output"))
    )
    (net (code "157") (name "unconnected-(IC2-~{SUSPEND}-Pad11)") (class "Default")
      (node (ref "IC2") (pin "11") (pinfunction "~{SUSPEND}_11") (pintype "output"))
    )
    (net (code "158") (name "unconnected-(JOYPAD1-Pad2)") (class "Default")
      (node (ref "JOYPAD1") (pin "2") (pinfunction "2_2") (pintype "passive"))
    )
    (net (code "159") (name "unconnected-(JOYPAD2-Pad2)") (class "Default")
      (node (ref "JOYPAD2") (pin "2") (pinfunction "2_2") (pintype "passive"))
    )
    (net (code "160") (name "unconnected-(JTAG-Pad6)") (class "Default")
      (node (ref "JTAG") (pin "6") (pinfunction "6_6") (pintype "passive"))
    )
    (net (code "161") (name "unconnected-(JTAG-Pad7)") (class "Default")
      (node (ref "JTAG") (pin "7") (pinfunction "7_7") (pintype "passive"))
    )
    (net (code "162") (name "unconnected-(JTAG-Pad8)") (class "Default")
      (node (ref "JTAG") (pin "8") (pinfunction "8_8") (pintype "passive"))
    )
    (net (code "163") (name "unconnected-(MIC_OUT-PadRING)") (class "Default")
      (node (ref "MIC_OUT") (pin "RING") (pinfunction "RING_RING") (pintype "passive"))
    )
    (net (code "164") (name "unconnected-(MIC_OUT-PadRING_SWITCH)") (class "Default")
      (node (ref "MIC_OUT") (pin "RING_SWITCH") (pinfunction "RING_SWITCH_RING_SWITCH") (pintype "passive"))
    )
    (net (code "165") (name "unconnected-(MIC_OUT-PadTIP_SWITCH)") (class "Default")
      (node (ref "MIC_OUT") (pin "TIP_SWITCH") (pinfunction "TIP_SWITCH_TIP_SWITCH") (pintype "passive"))
    )
    (net (code "166") (name "unconnected-(PS2-Pad2)") (class "Default")
      (node (ref "PS2") (pin "2") (pinfunction "2_2") (pintype "passive"))
    )
    (net (code "167") (name "unconnected-(PS2-Pad6)") (class "Default")
      (node (ref "PS2") (pin "6") (pinfunction "6_6") (pintype "passive"))
    )
    (net (code "168") (name "unconnected-(S1-Pad1)") (class "Default")
      (node (ref "S1") (pin "1") (pinfunction "1_1") (pintype "bidirectional"))
    )
    (net (code "169") (name "unconnected-(SERIAL-Pad1)") (class "Default")
      (node (ref "SERIAL") (pin "1") (pinfunction "1_1") (pintype "passive"))
    )
    (net (code "170") (name "unconnected-(SERIAL-Pad4)") (class "Default")
      (node (ref "SERIAL") (pin "4") (pinfunction "4_4") (pintype "passive"))
    )
    (net (code "171") (name "unconnected-(SERIAL-Pad6)") (class "Default")
      (node (ref "SERIAL") (pin "6") (pinfunction "6_6") (pintype "passive"))
    )
    (net (code "172") (name "unconnected-(SERIAL-Pad9)") (class "Default")
      (node (ref "SERIAL") (pin "9") (pinfunction "9_9") (pintype "passive"))
    )
    (net (code "173") (name "unconnected-(TAPE_IN-PadRING)") (class "Default")
      (node (ref "TAPE_IN") (pin "RING") (pinfunction "RING_RING") (pintype "passive"))
    )
    (net (code "174") (name "unconnected-(TAPE_IN-PadRING_SWITCH)") (class "Default")
      (node (ref "TAPE_IN") (pin "RING_SWITCH") (pinfunction "RING_SWITCH_RING_SWITCH") (pintype "passive"))
    )
    (net (code "175") (name "unconnected-(TAPE_IN-PadTIP_SWITCH)") (class "Default")
      (node (ref "TAPE_IN") (pin "TIP_SWITCH") (pinfunction "TIP_SWITCH_TIP_SWITCH") (pintype "passive"))
    )
    (net (code "176") (name "unconnected-(TAPE_OUT-PadRING_SWITCH)") (class "Default")
      (node (ref "TAPE_OUT") (pin "RING_SWITCH") (pinfunction "RING_SWITCH_RING_SWITCH") (pintype "passive"))
    )
    (net (code "177") (name "unconnected-(TAPE_OUT-PadTIP_SWITCH)") (class "Default")
      (node (ref "TAPE_OUT") (pin "TIP_SWITCH") (pinfunction "TIP_SWITCH_TIP_SWITCH") (pintype "passive"))
    )
    (net (code "178") (name "unconnected-(U1-IO-Pad10)") (class "Default")
      (node (ref "U1") (pin "10") (pinfunction "IO_10") (pintype "bidirectional"))
    )
    (net (code "179") (name "unconnected-(U1-IO-Pad11)") (class "Default")
      (node (ref "U1") (pin "11") (pinfunction "IO_11") (pintype "bidirectional"))
    )
    (net (code "180") (name "unconnected-(U1-IO-Pad28)") (class "Default")
      (node (ref "U1") (pin "28") (pinfunction "IO_28") (pintype "bidirectional"))
    )
    (net (code "181") (name "unconnected-(U1-IO-Pad73)") (class "Default")
      (node (ref "U1") (pin "73") (pinfunction "IO_73") (pintype "bidirectional"))
    )
    (net (code "182") (name "unconnected-(U1-IO-Pad74)") (class "Default")
      (node (ref "U1") (pin "74") (pinfunction "IO_74") (pintype "bidirectional"))
    )
    (net (code "183") (name "unconnected-(U1-IO-Pad128)") (class "Default")
      (node (ref "U1") (pin "128") (pinfunction "IO_128") (pintype "bidirectional"))
    )
    (net (code "184") (name "unconnected-(U1-IO-Pad129)") (class "Default")
      (node (ref "U1") (pin "129") (pinfunction "IO_129") (pintype "bidirectional"))
    )
    (net (code "185") (name "unconnected-(U1-IO-Pad132)") (class "Default")
      (node (ref "U1") (pin "132") (pinfunction "IO_132") (pintype "bidirectional"))
    )
    (net (code "186") (name "unconnected-(U1-IO-Pad133)") (class "Default")
      (node (ref "U1") (pin "133") (pinfunction "IO_133") (pintype "bidirectional"))
    )
    (net (code "187") (name "unconnected-(U1-IO-Pad135)") (class "Default")
      (node (ref "U1") (pin "135") (pinfunction "IO_135") (pintype "bidirectional"))
    )
    (net (code "188") (name "unconnected-(U1-IO-Pad136)") (class "Default")
      (node (ref "U1") (pin "136") (pinfunction "IO_136") (pintype "bidirectional"))
    )
    (net (code "189") (name "unconnected-(U1-IO-Pad137)") (class "Default")
      (node (ref "U1") (pin "137") (pinfunction "IO_137") (pintype "bidirectional"))
    )
    (net (code "190") (name "unconnected-(U1-IO-Pad138)") (class "Default")
      (node (ref "U1") (pin "138") (pinfunction "IO_138") (pintype "bidirectional"))
    )
    (net (code "191") (name "unconnected-(U1-IO-Pad141)") (class "Default")
      (node (ref "U1") (pin "141") (pinfunction "IO_141") (pintype "bidirectional"))
    )
    (net (code "192") (name "unconnected-(U1-IO-Pad142)") (class "Default")
      (node (ref "U1") (pin "142") (pinfunction "IO_142") (pintype "bidirectional"))
    )
    (net (code "193") (name "unconnected-(VGA-Pad4)") (class "Default")
      (node (ref "VGA") (pin "4") (pinfunction "4_4") (pintype "passive"))
    )
    (net (code "194") (name "unconnected-(VGA-Pad9)") (class "Default")
      (node (ref "VGA") (pin "9") (pinfunction "9_9") (pintype "passive"))
    )
    (net (code "195") (name "unconnected-(VGA-Pad11)") (class "Default")
      (node (ref "VGA") (pin "11") (pinfunction "11_11") (pintype "passive"))
    )
    (net (code "196") (name "unconnected-(VGA-Pad12)") (class "Default")
      (node (ref "VGA") (pin "12") (pinfunction "12_12") (pintype "passive"))
    )
    (net (code "197") (name "unconnected-(VGA-Pad15)") (class "Default")
      (node (ref "VGA") (pin "15") (pinfunction "15_15") (pintype "passive"))
    )
  )
)
